# module_alu.net
KiCad netlist of a schematic drawn in EAGLE
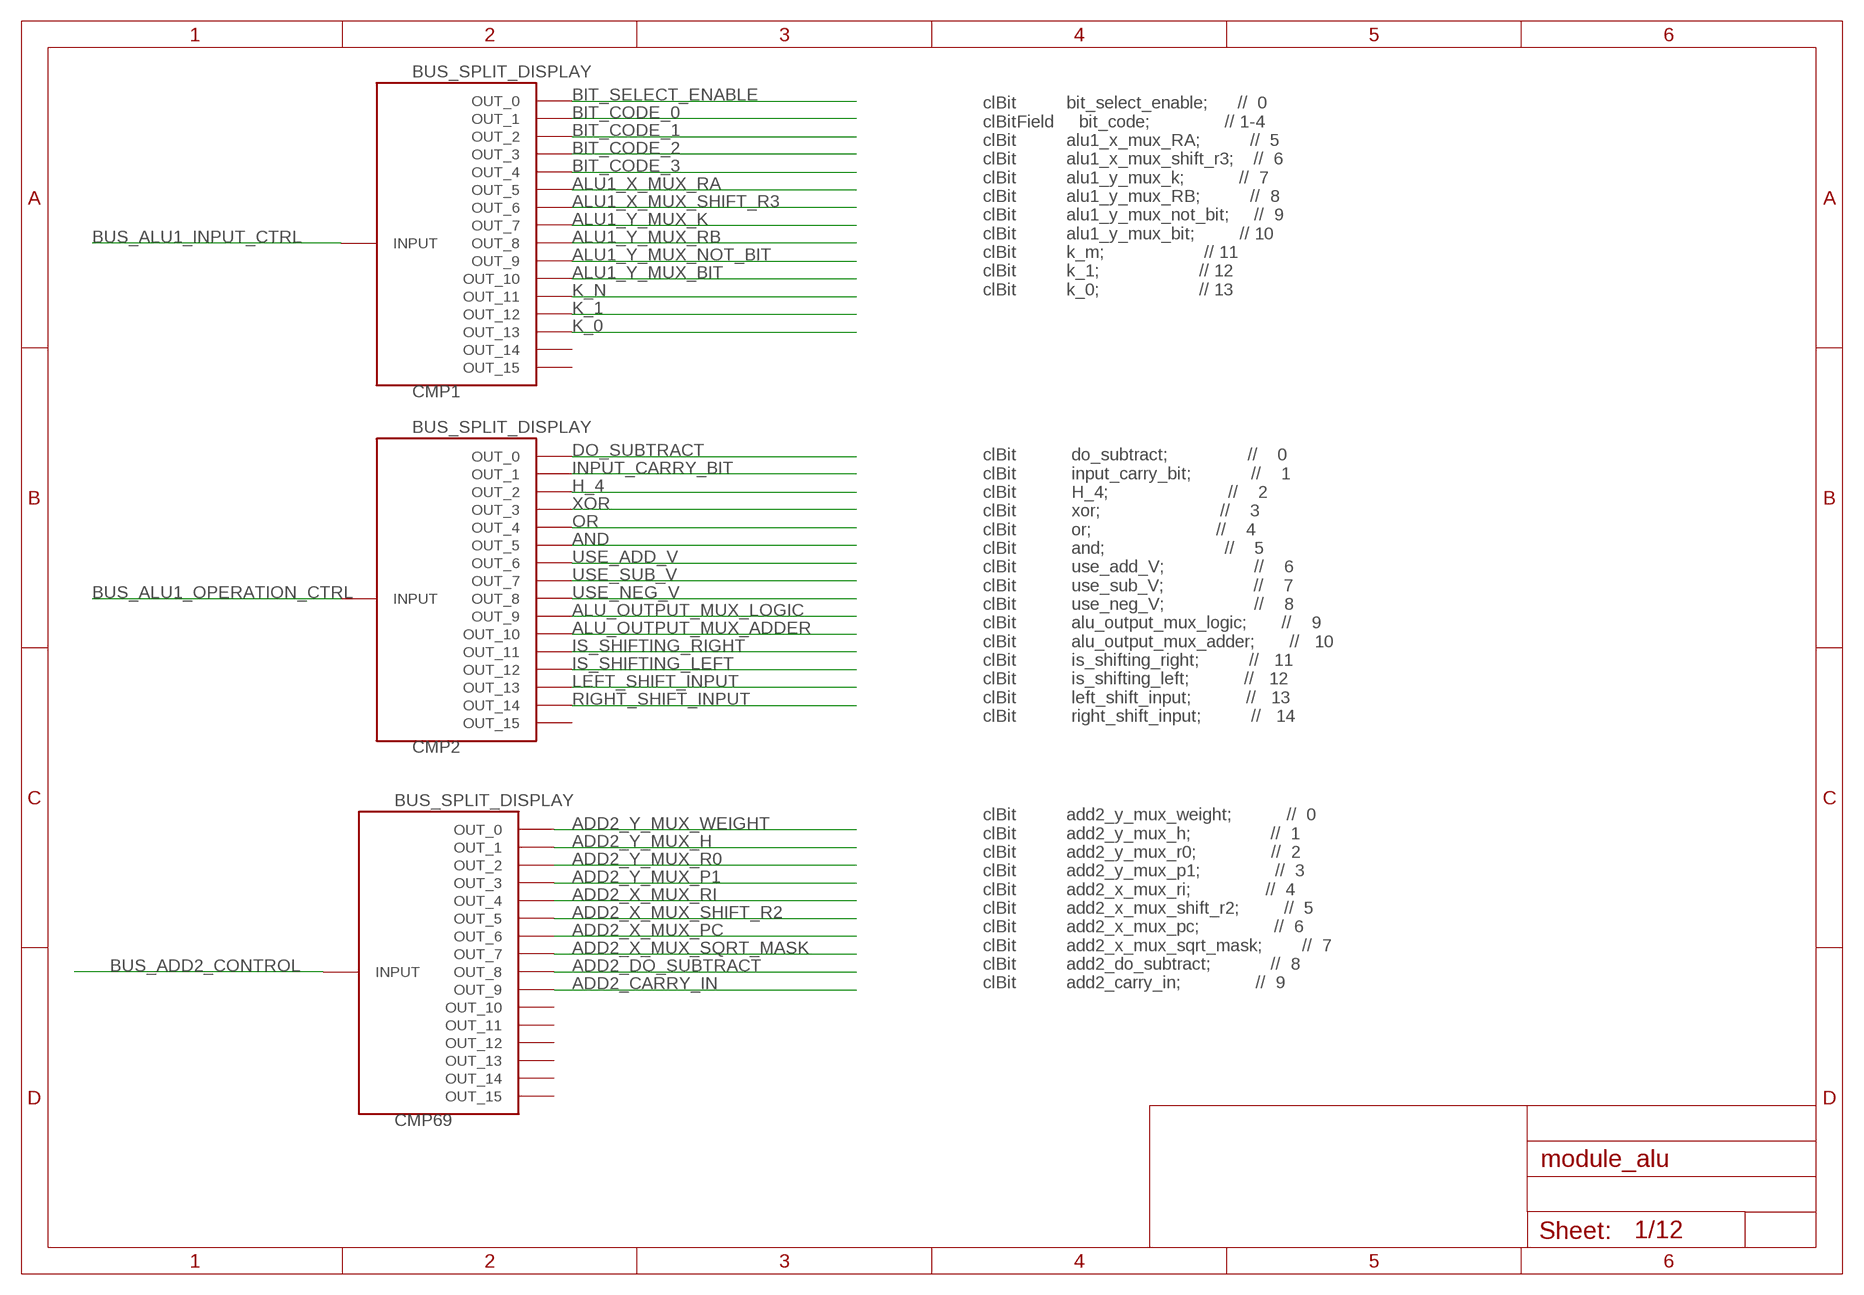
[diagram p0: schematic, sheet 1]
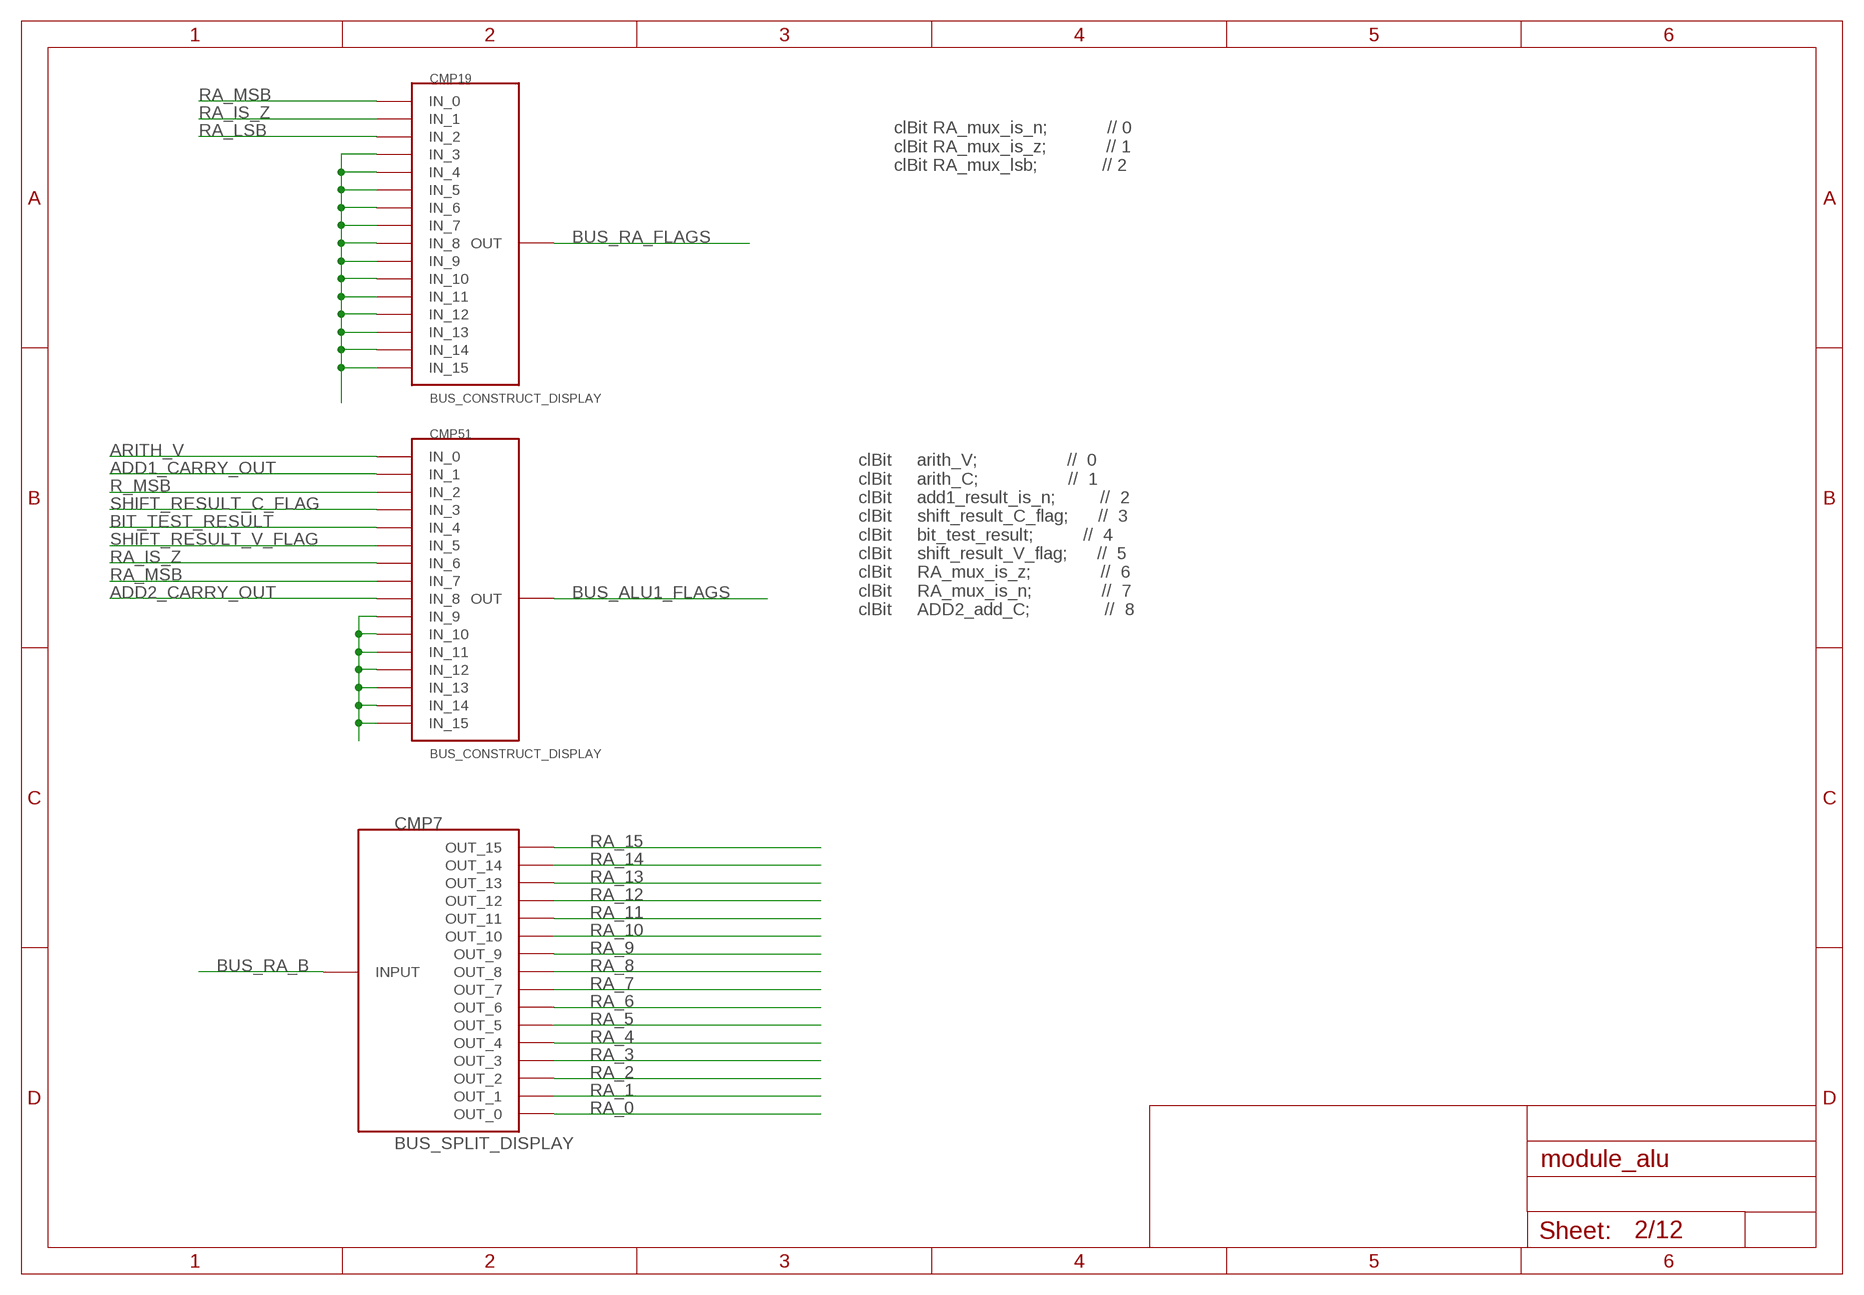
[diagram p1: schematic, sheet 2]
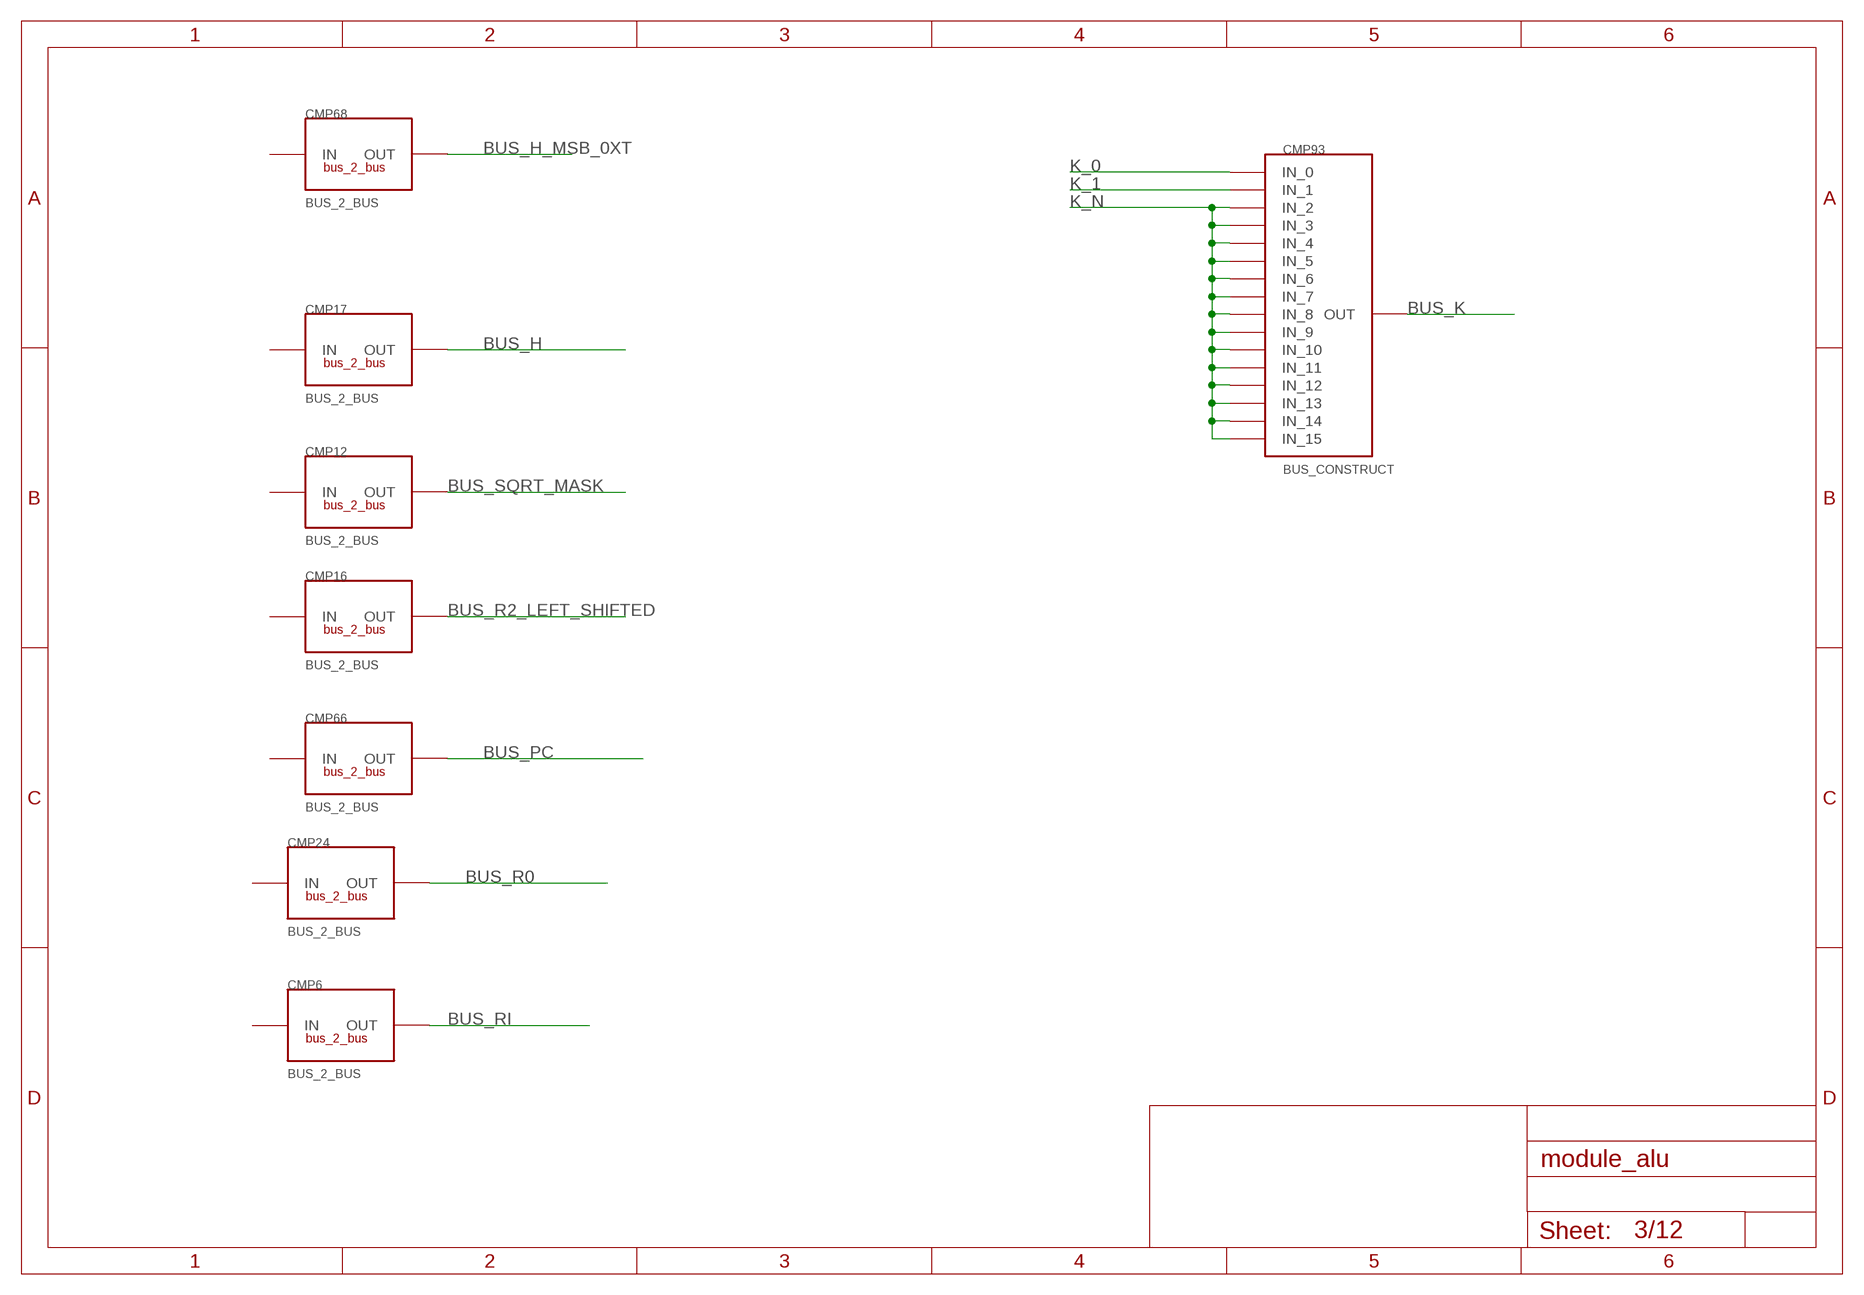
[diagram p2: schematic, sheet 3]
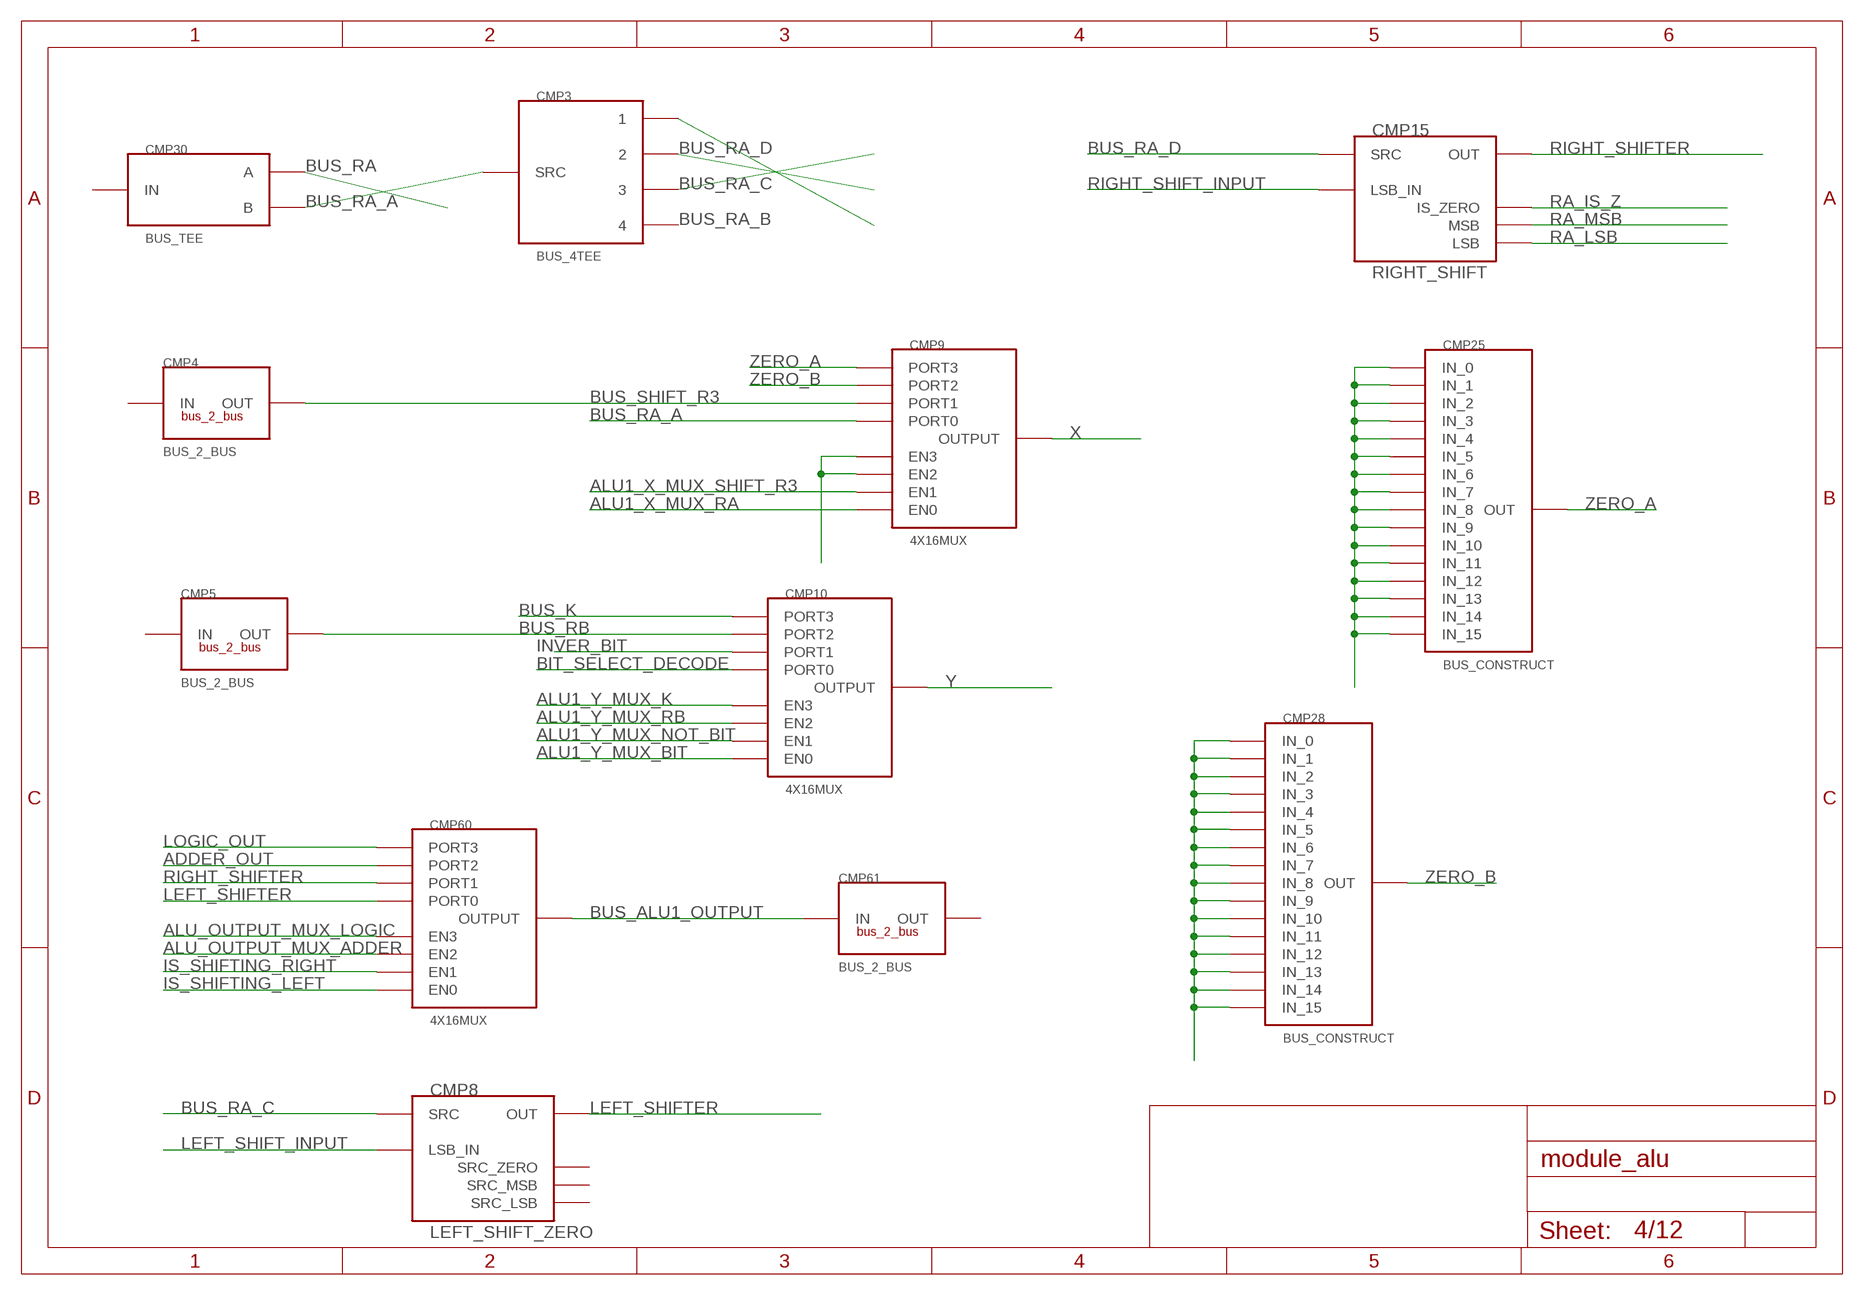
[diagram p3: schematic, sheet 4]
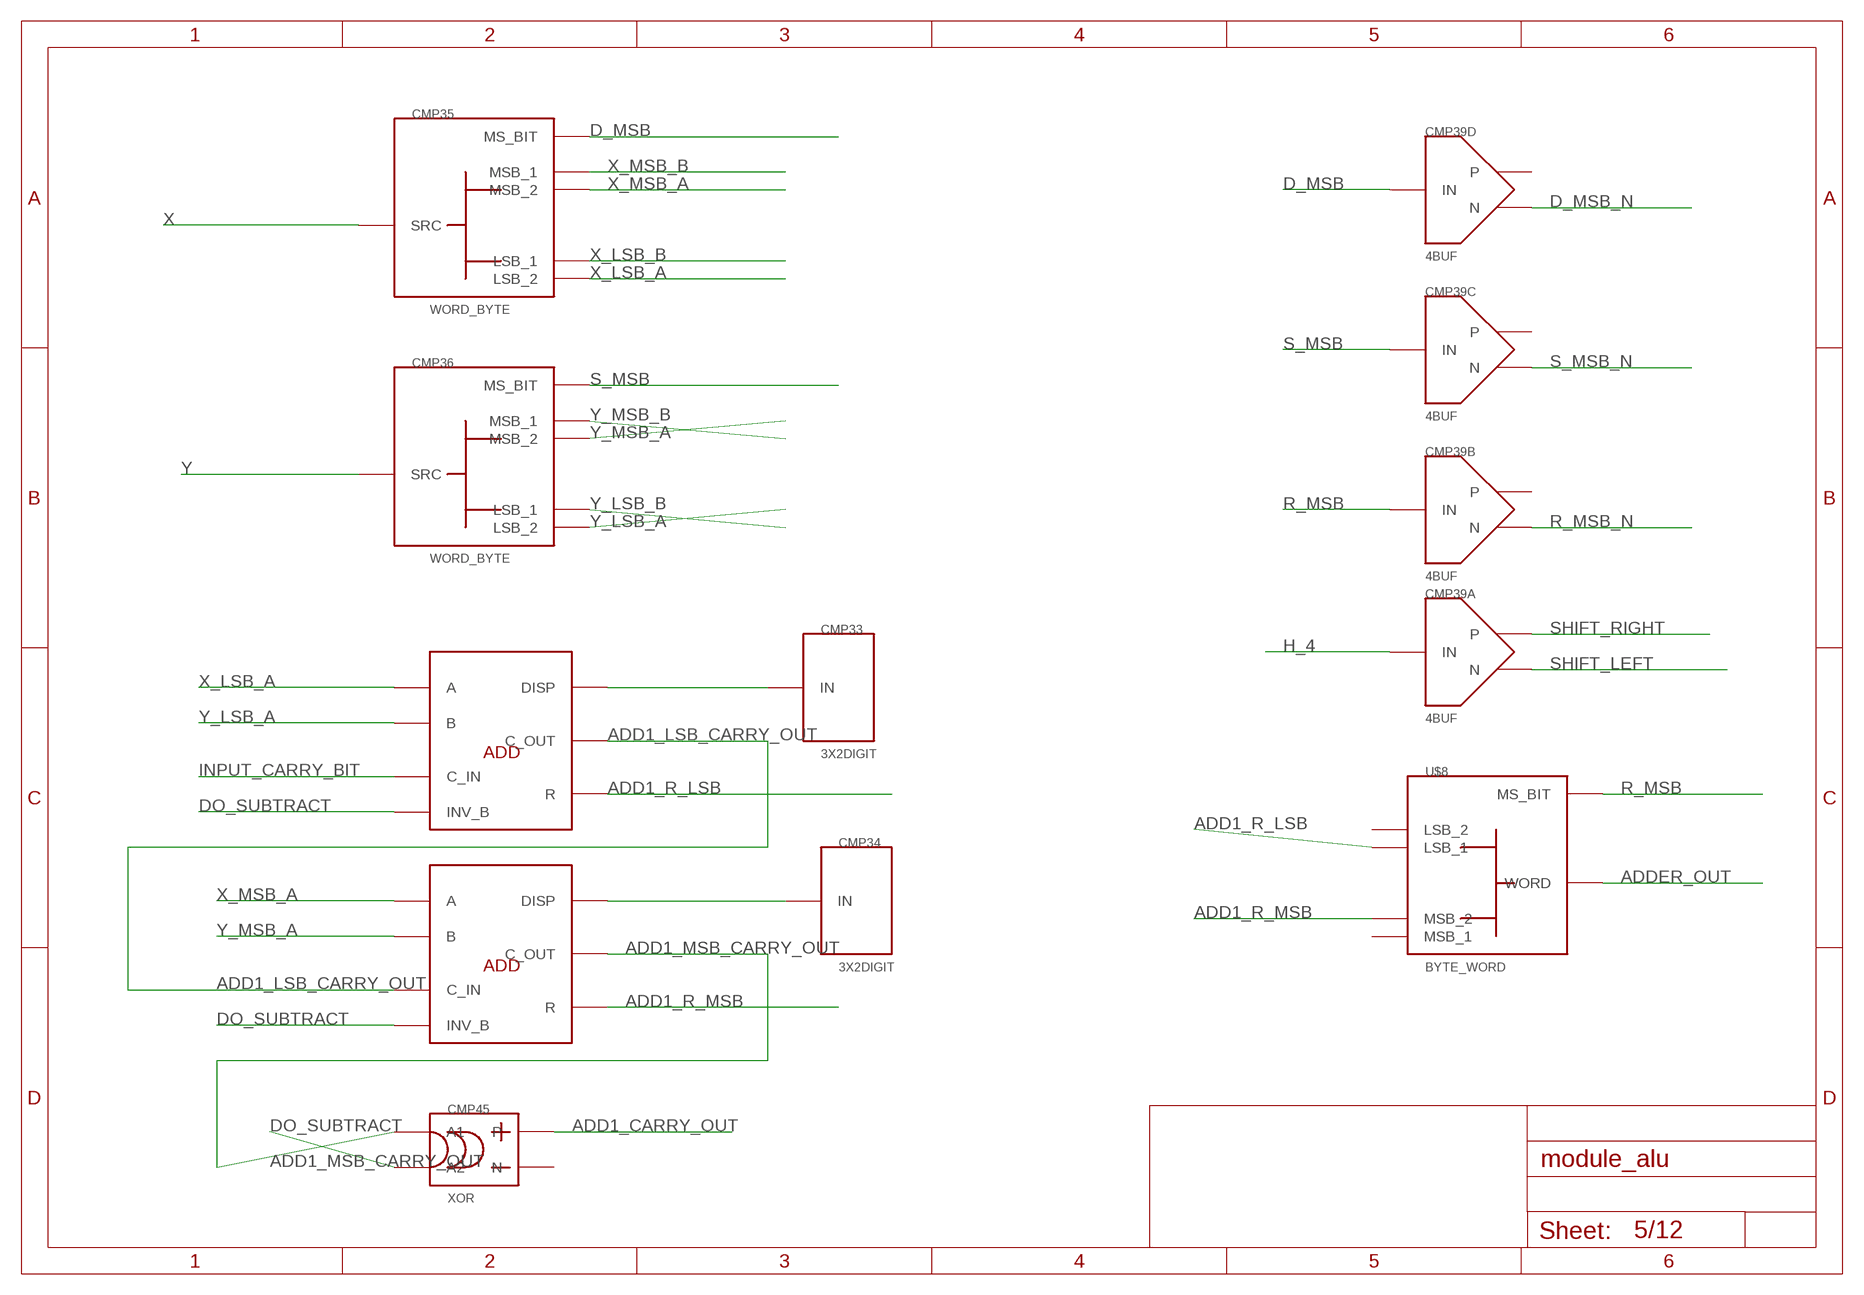
[diagram p4: schematic, sheet 5]
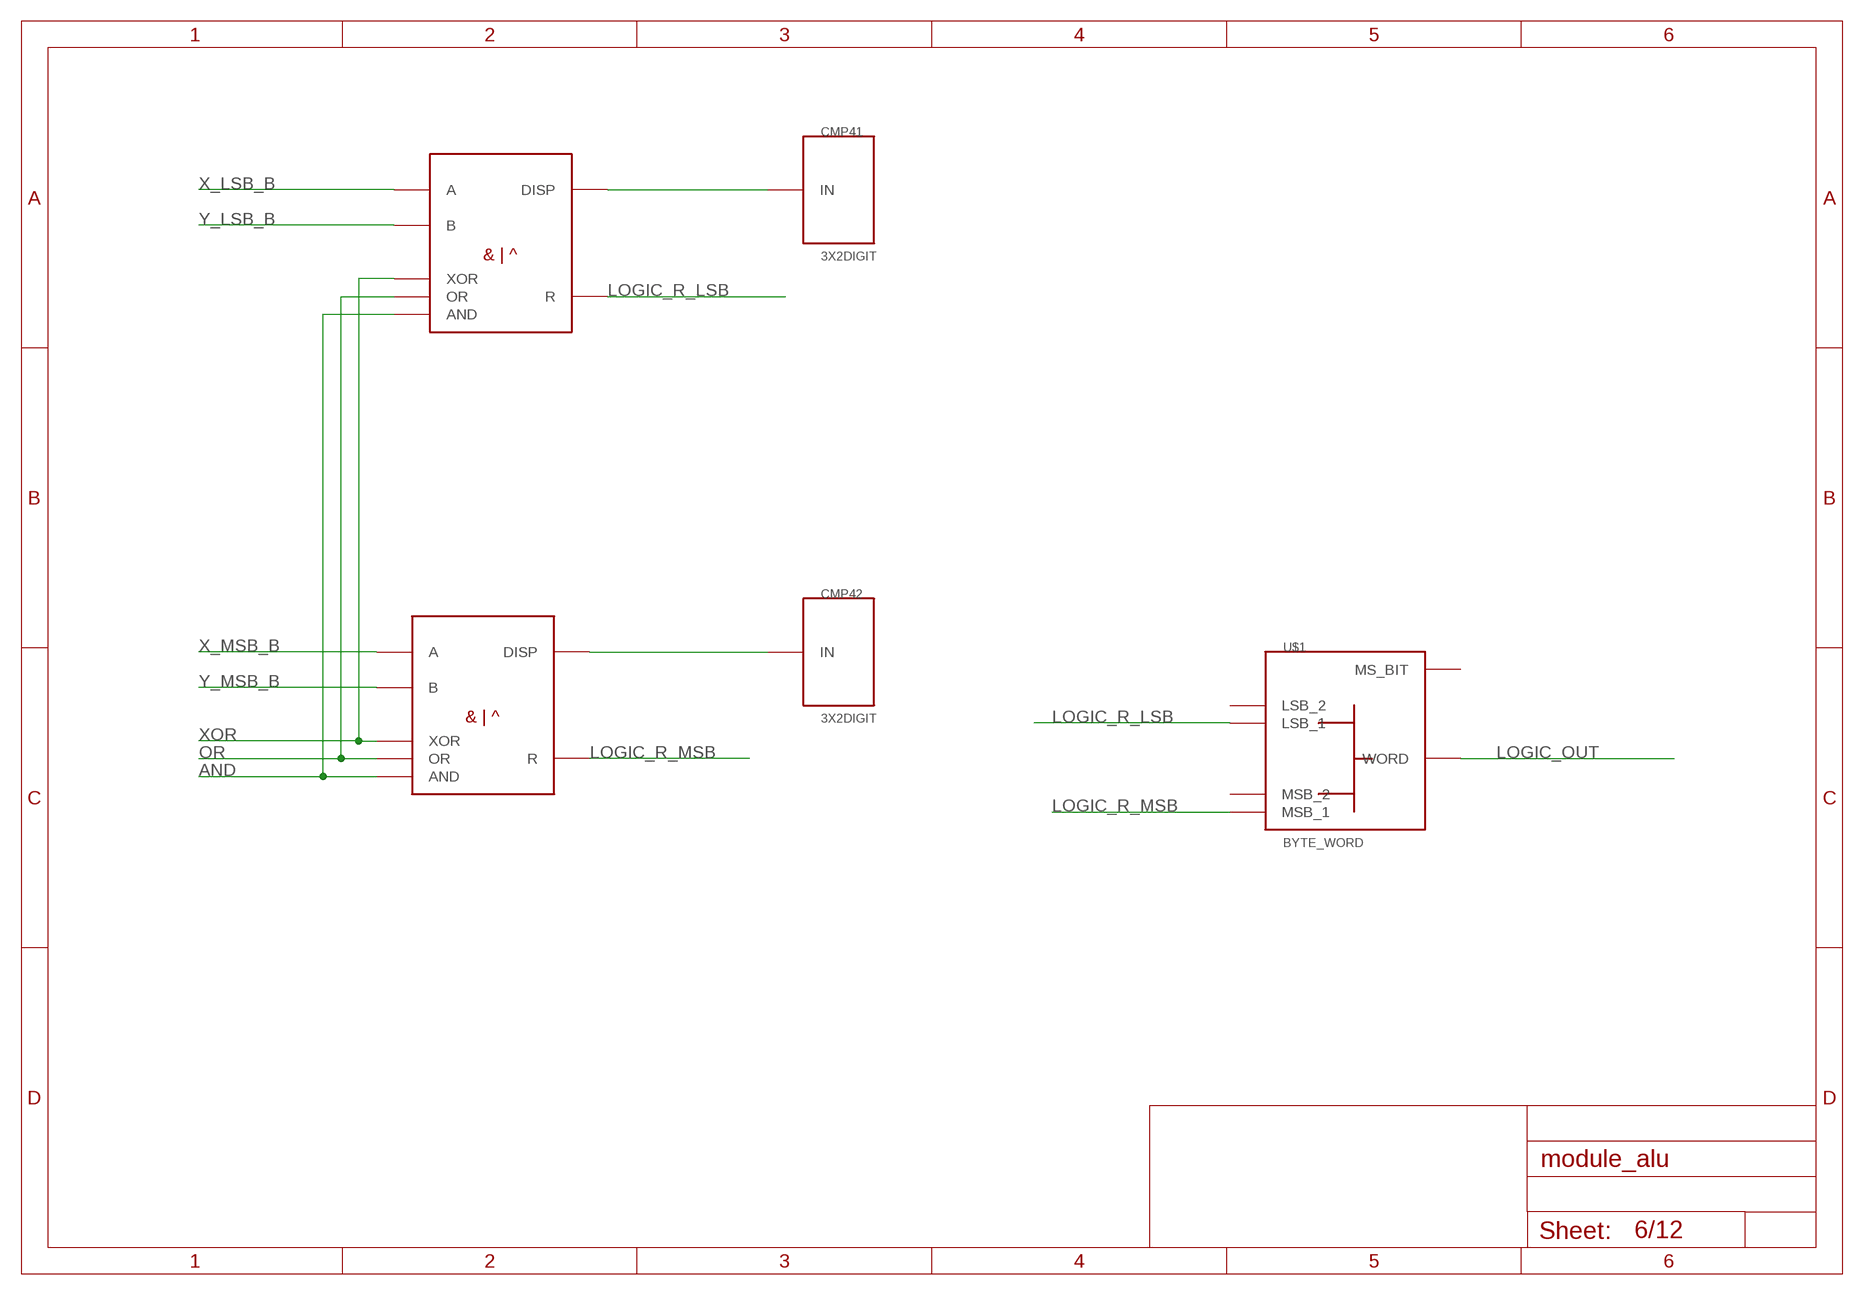
[diagram p5: schematic, sheet 6]
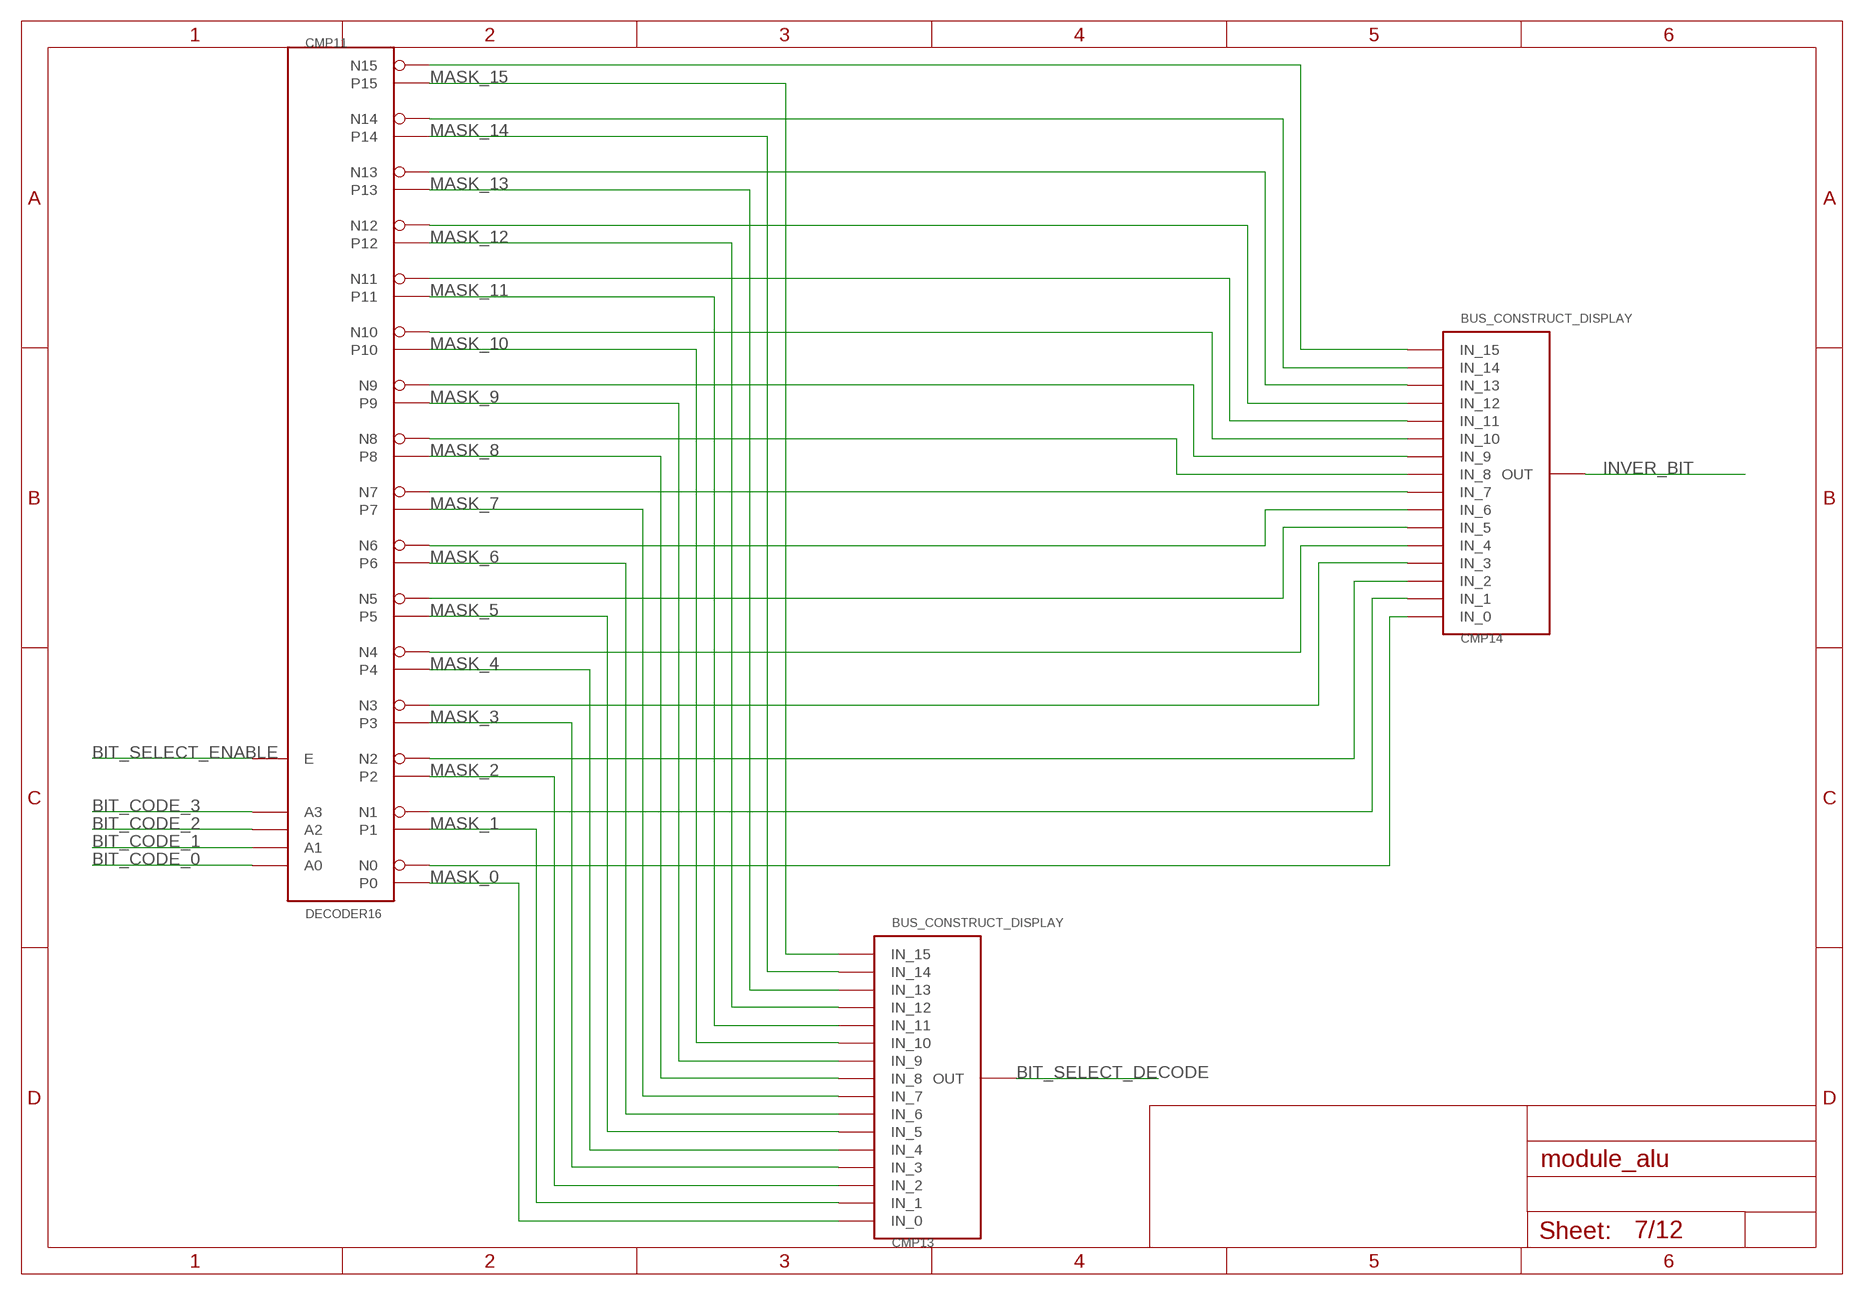
[diagram p6: schematic, sheet 7]
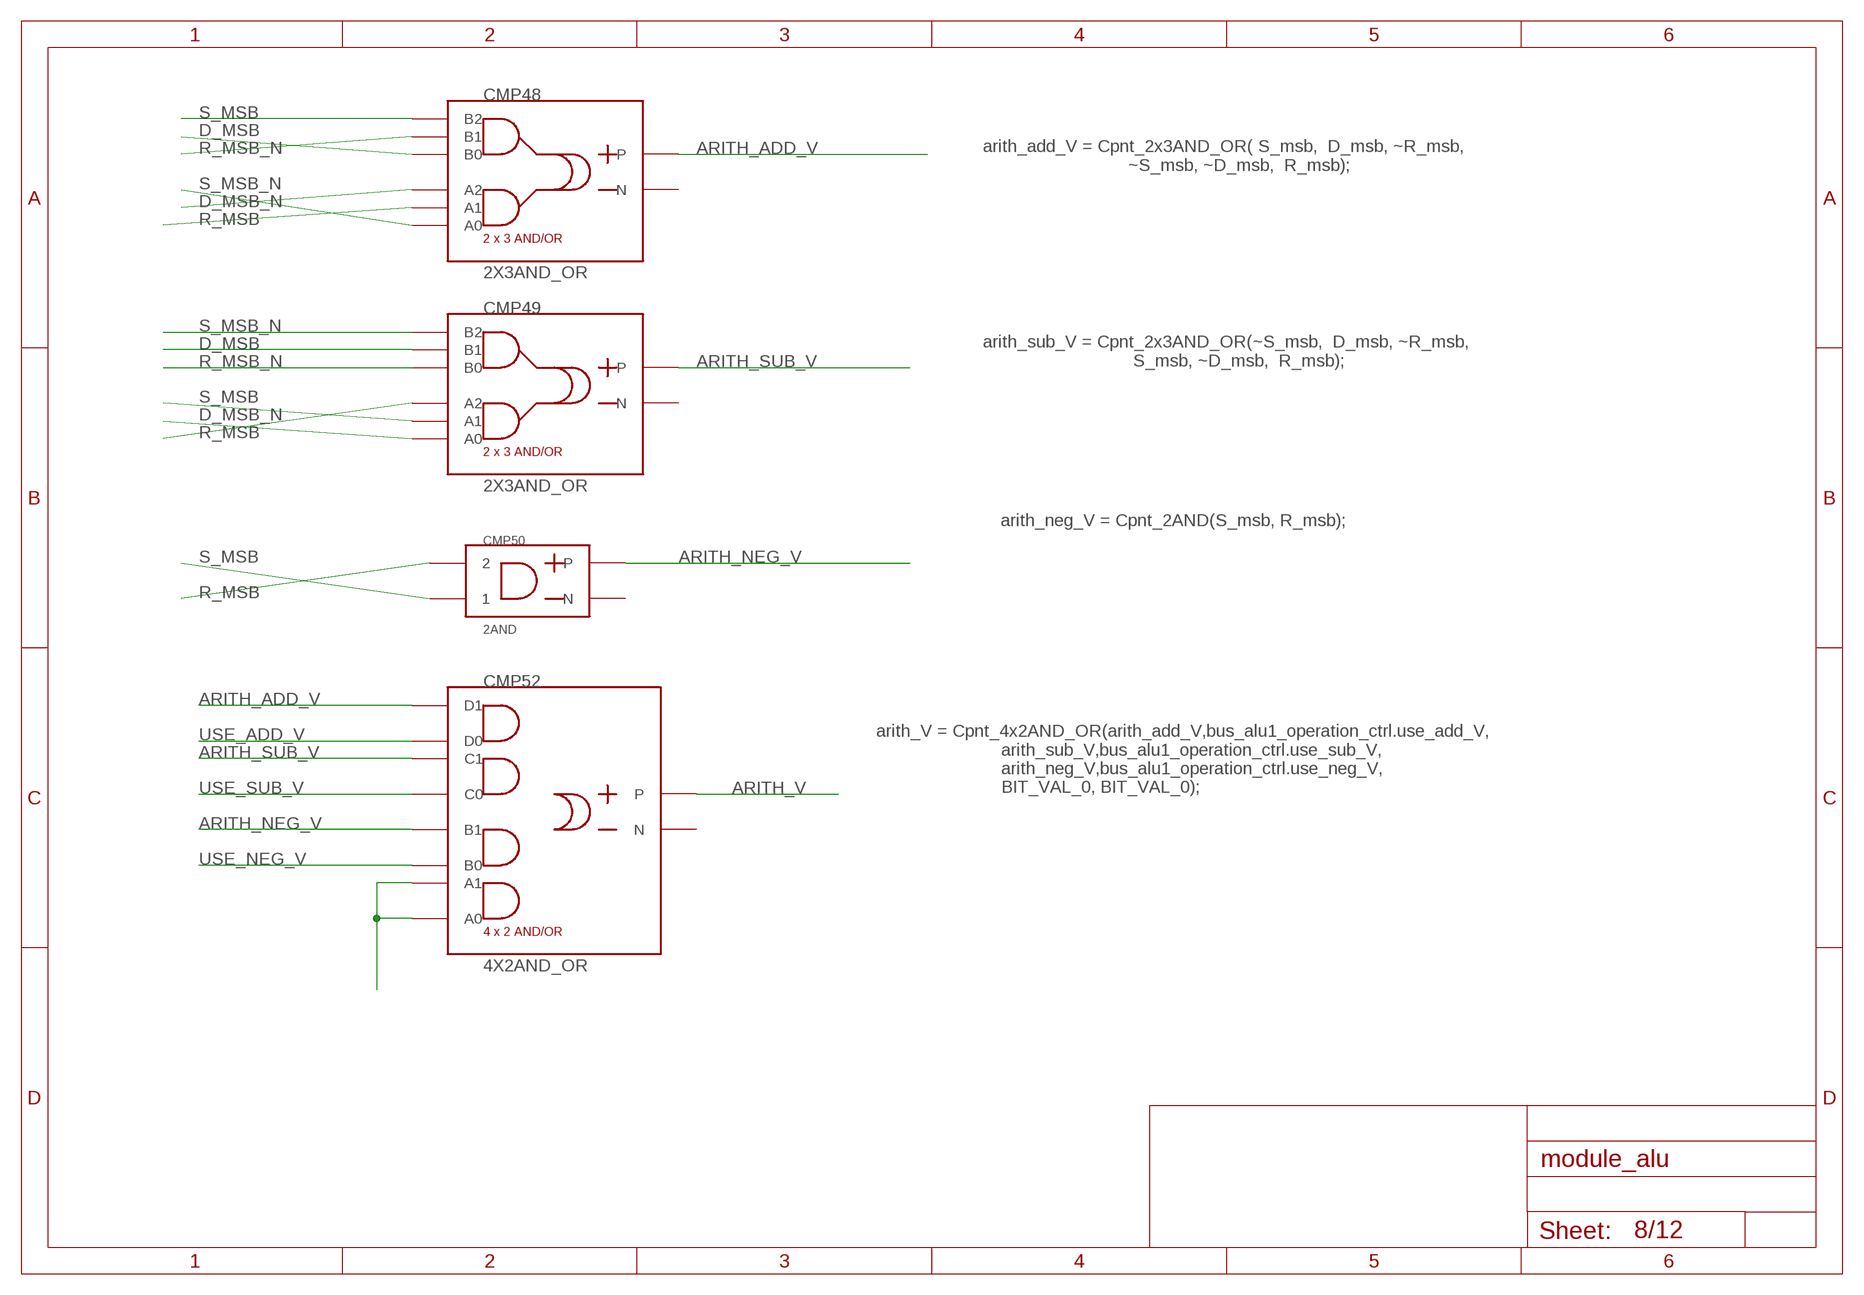
[diagram p7: schematic, sheet 8]
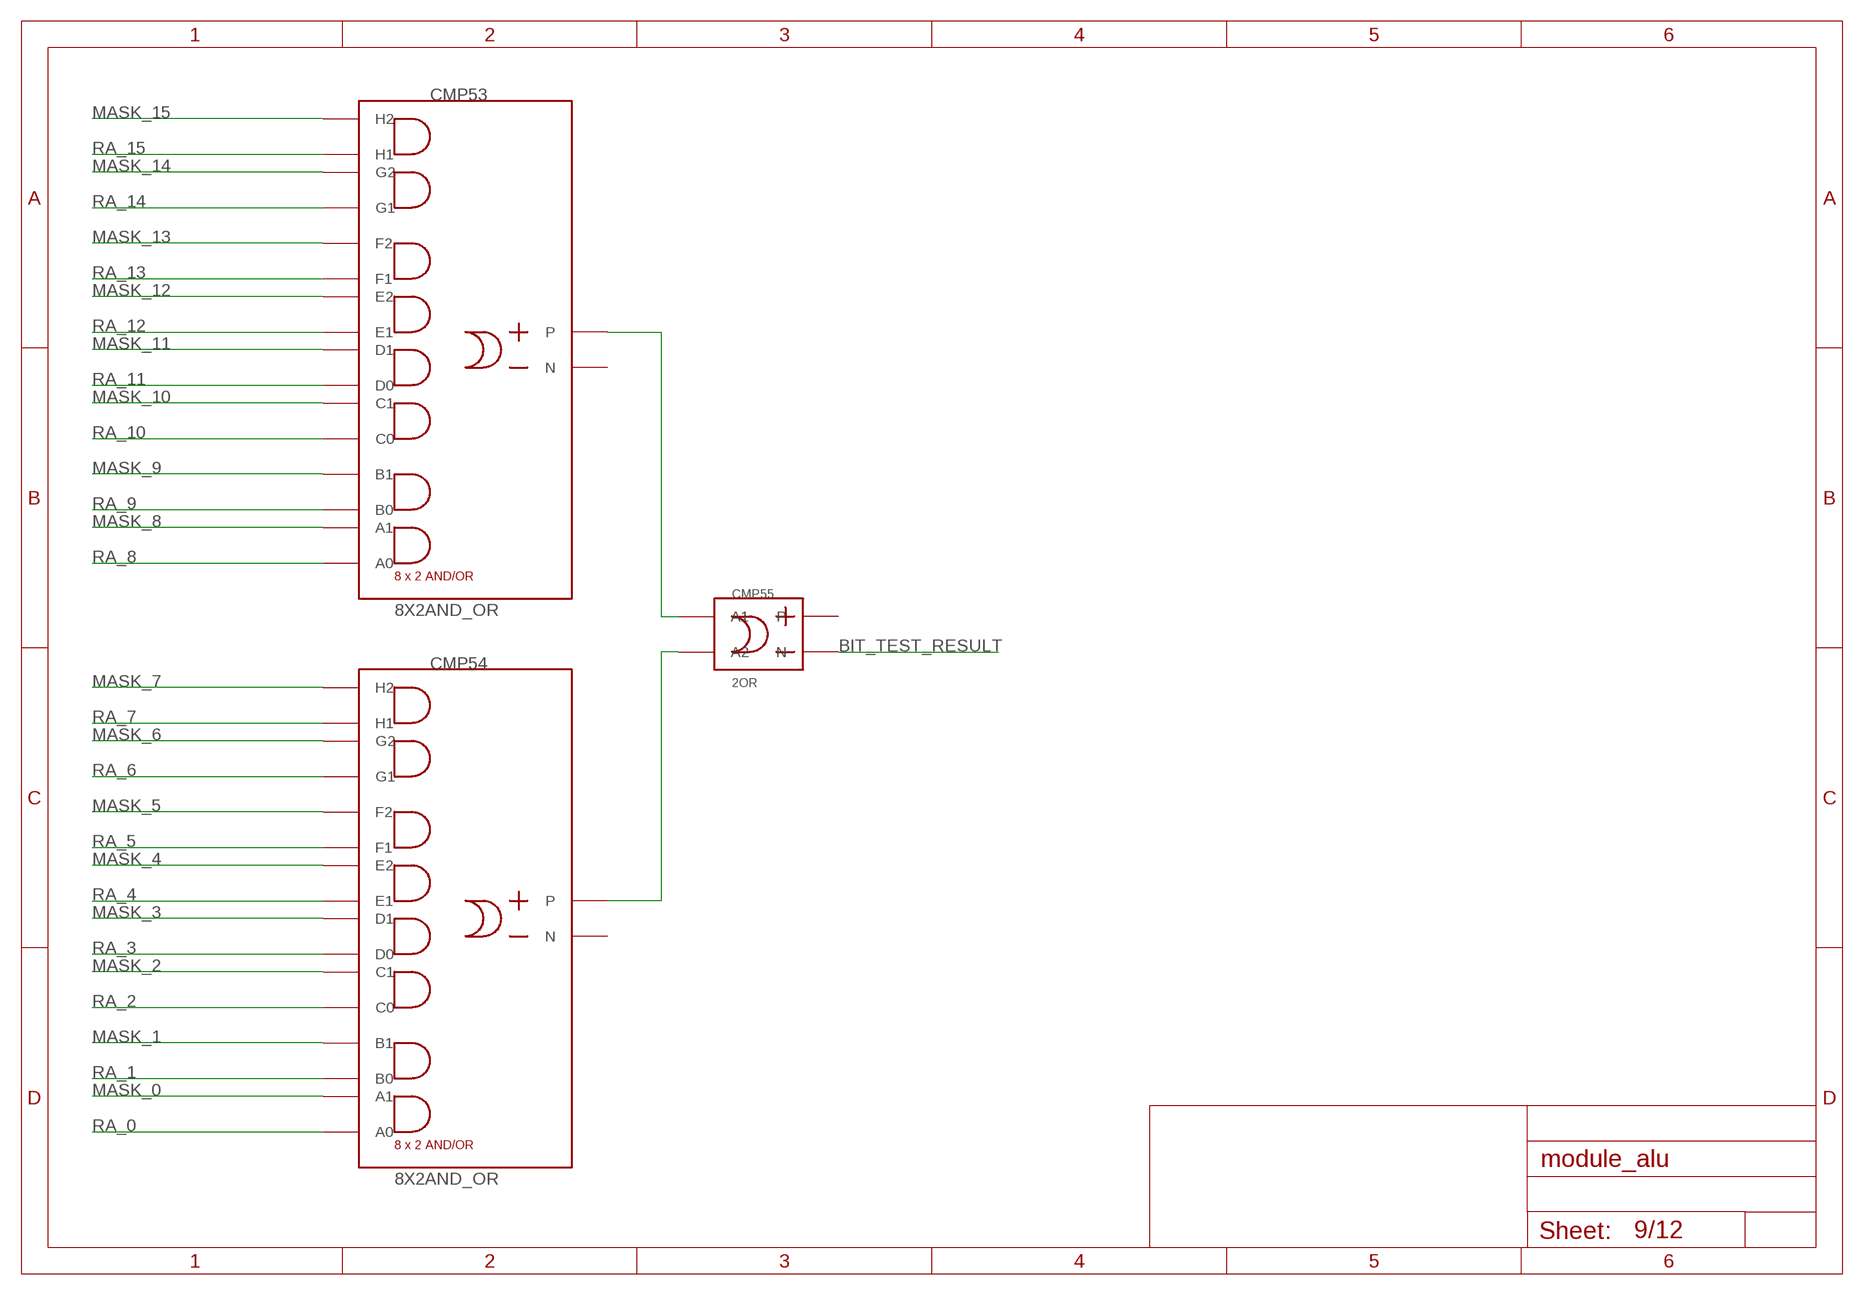
[diagram p8: schematic, sheet 9]
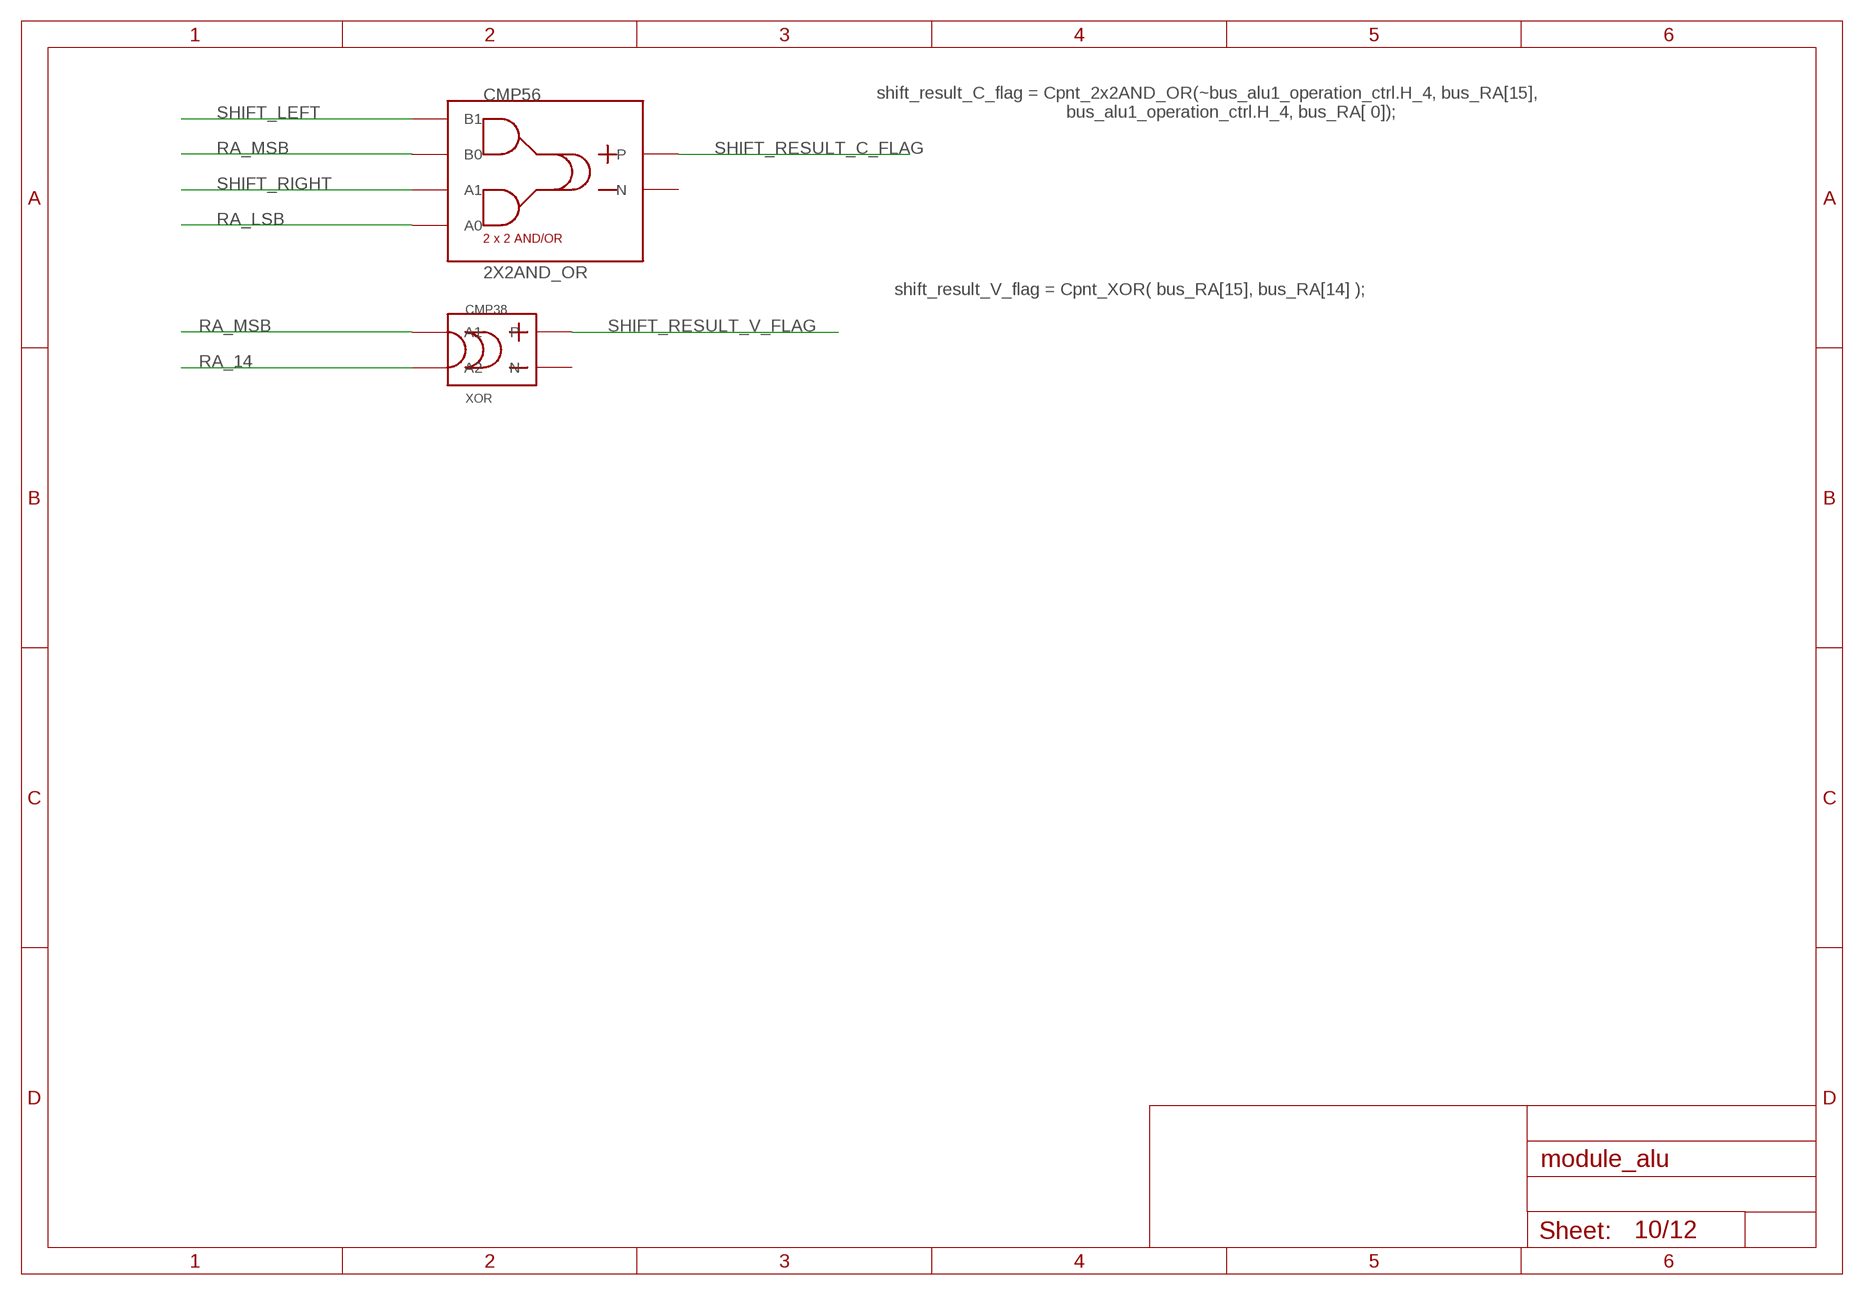
[diagram p9: schematic, sheet 10]
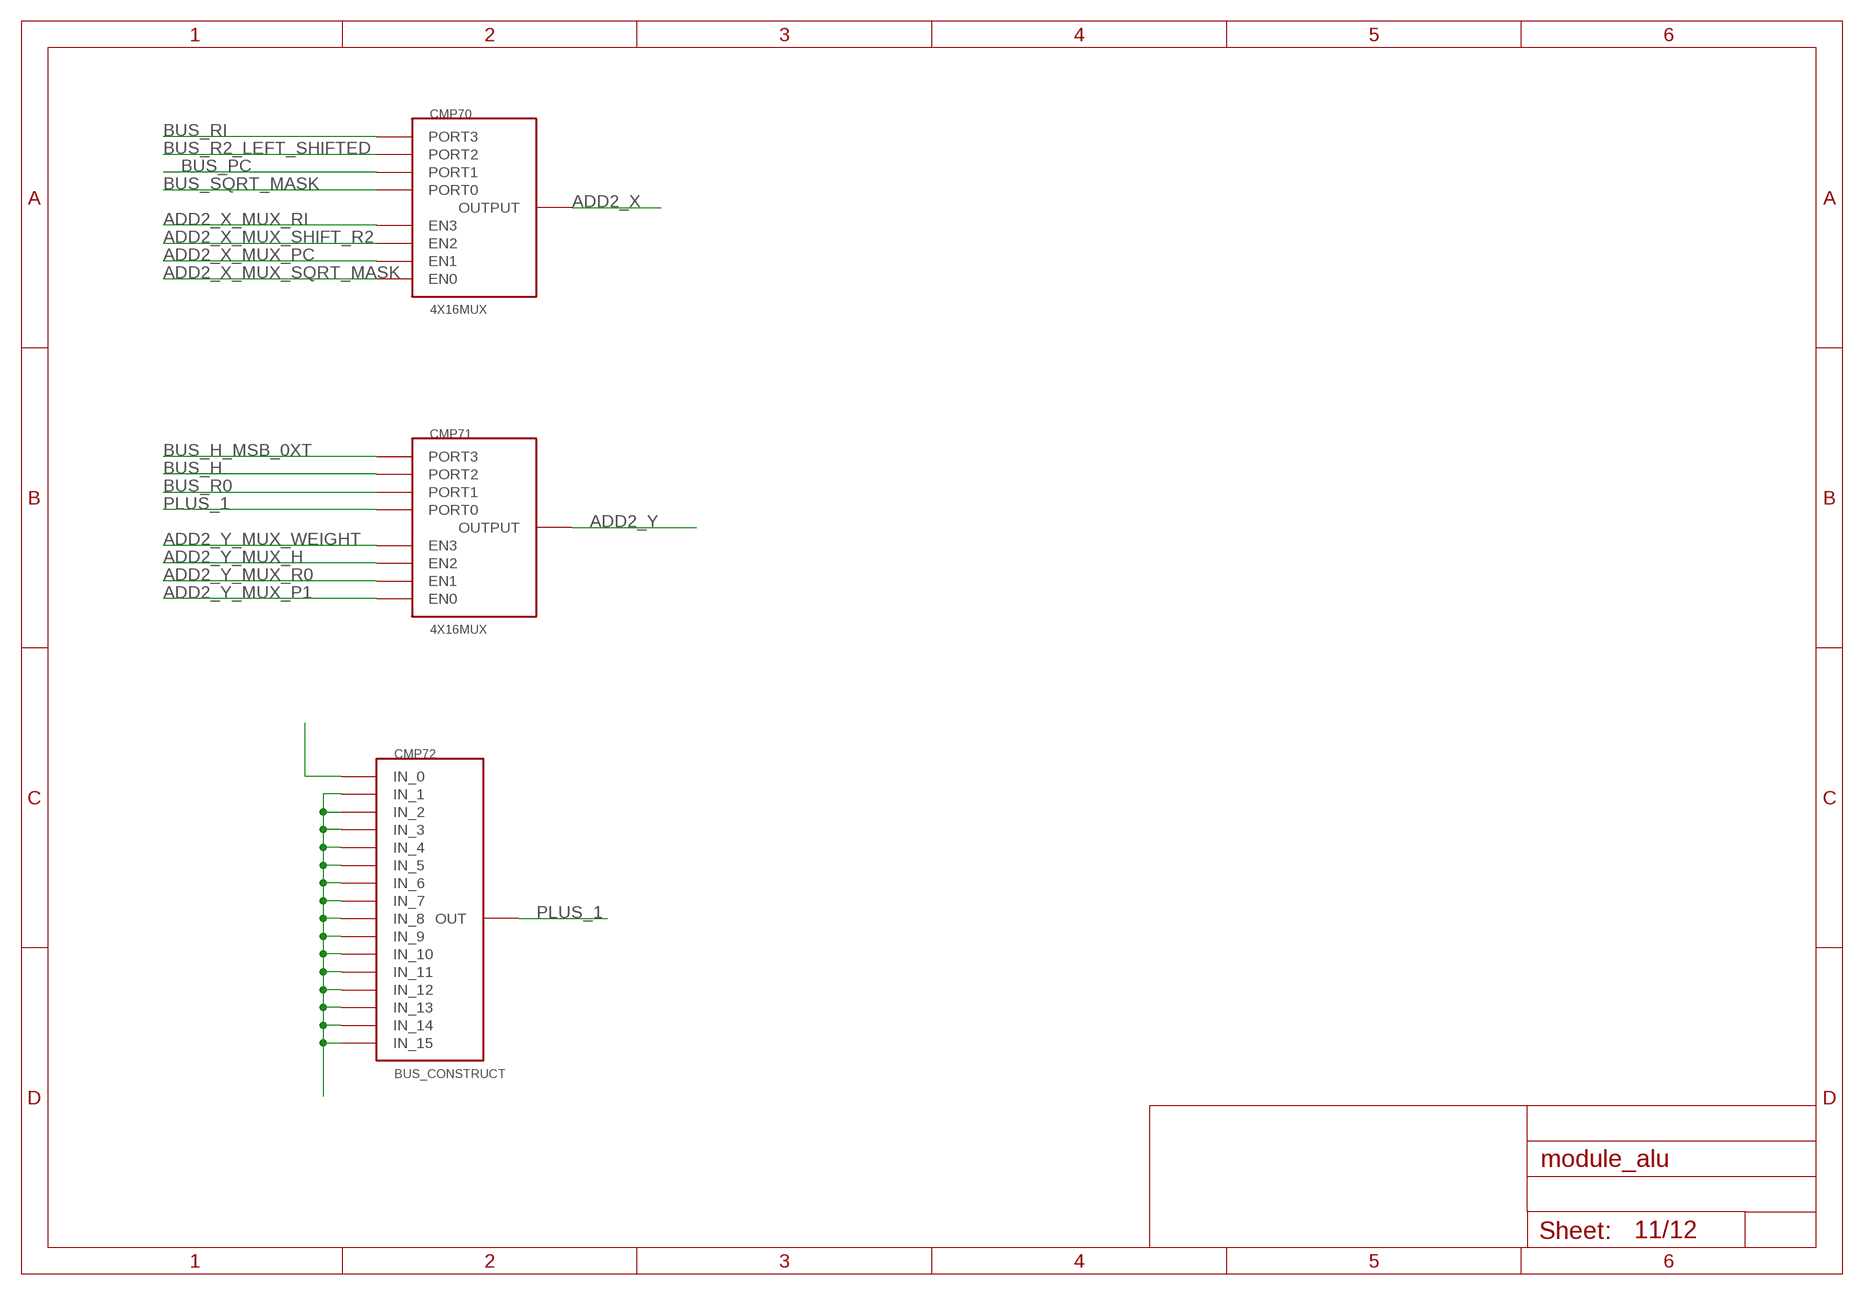
[diagram p10: schematic, sheet 11]
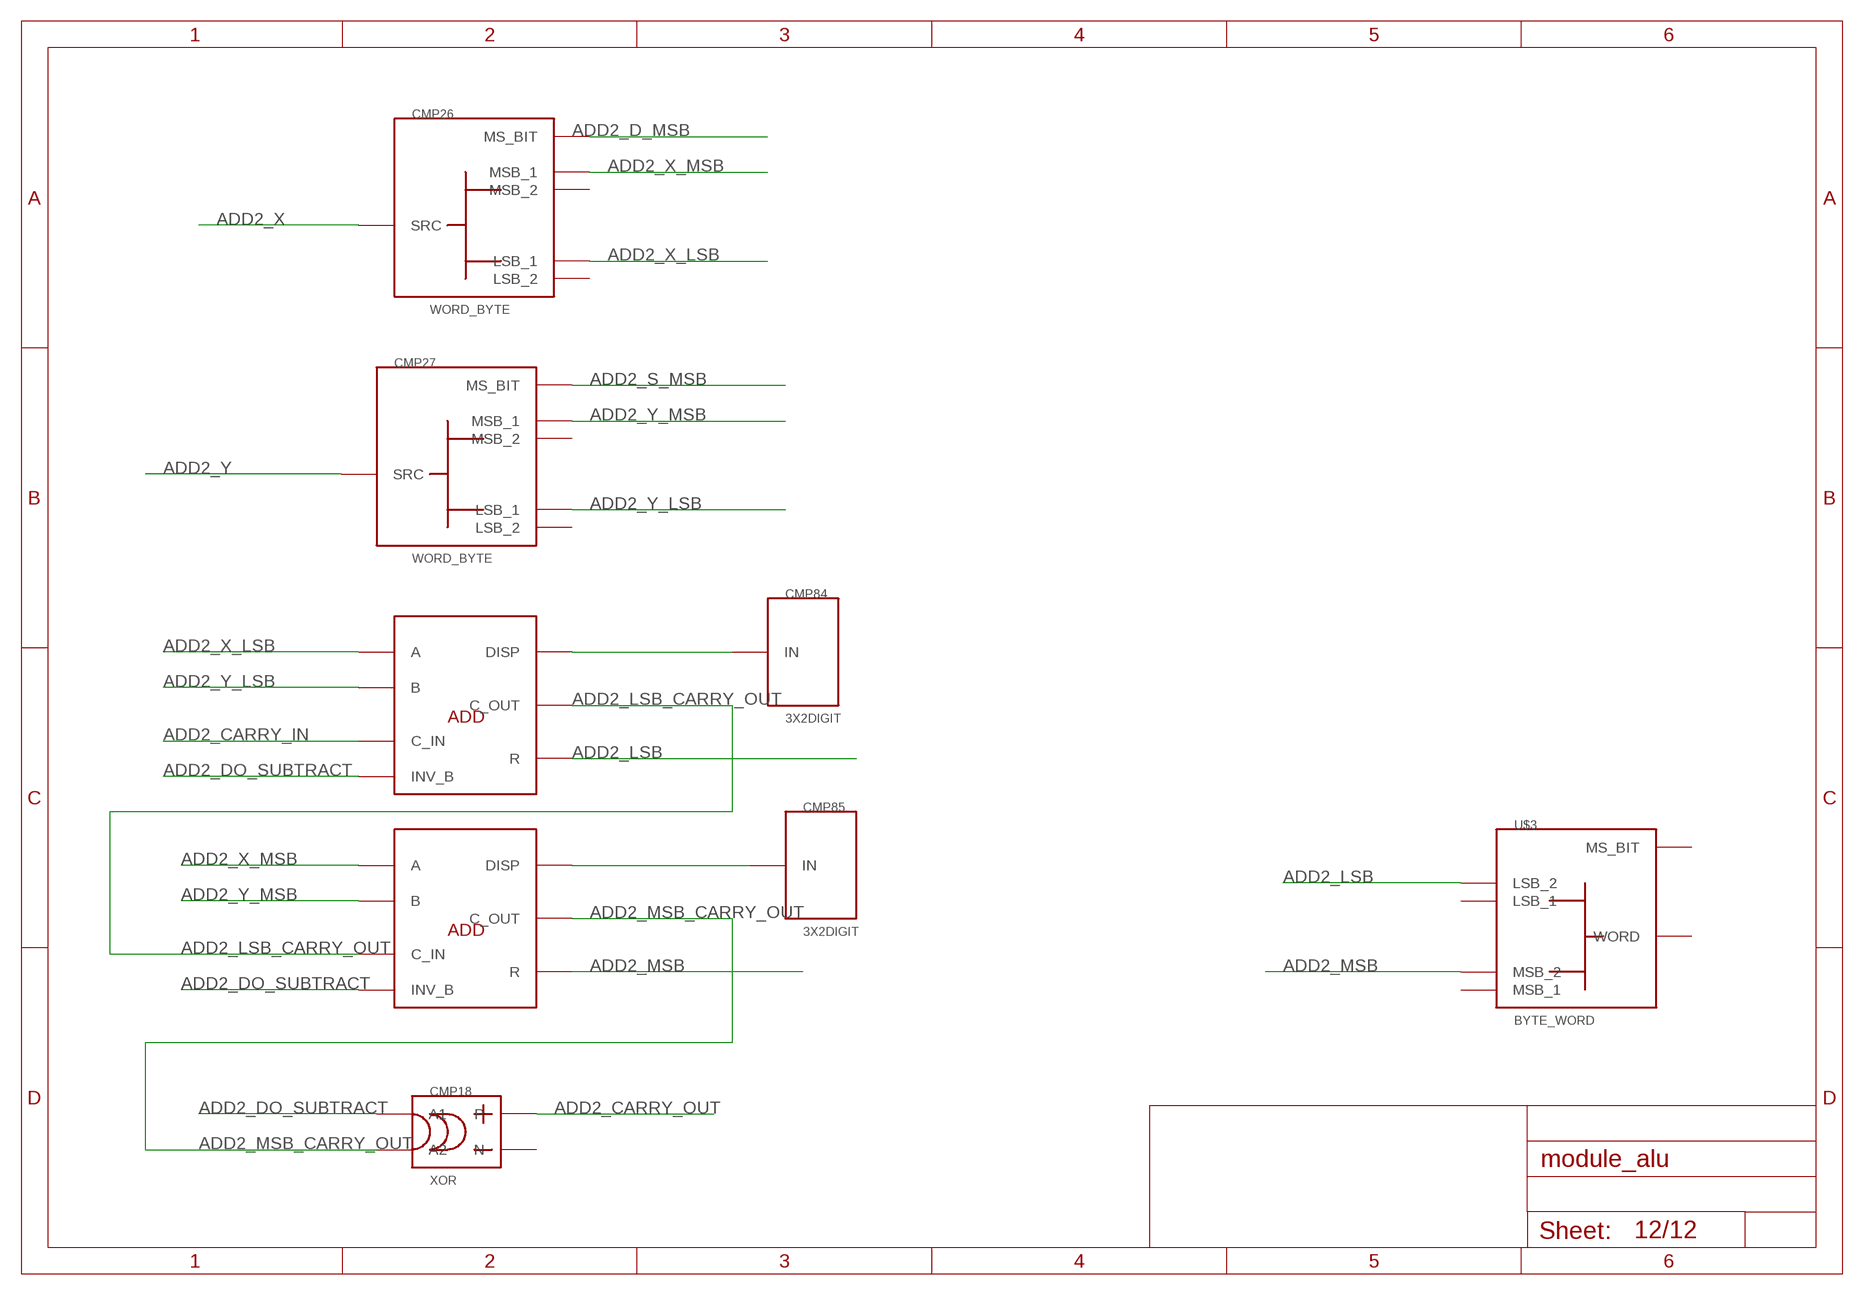
[diagram p11: schematic, sheet 12]

(export (version "E")
  (design (tool "Eeschema 10.0.6"))
  (components
    (comp (ref "CMP3")
      (value "BUS_4TEE")
      (footprint "eagle-import:BUS_4TEE")
      (libsource (lib "eagle-import") (part "BUS_4TEE"))
    )
    (comp (ref "CMP4")
      (value "BUS_2_BUS")
      (footprint "eagle-import:BUS2BUS")
      (libsource (lib "eagle-import") (part "BUS_2_BUS"))
    )
    (comp (ref "CMP5")
      (value "BUS_2_BUS")
      (footprint "eagle-import:BUS2BUS")
      (libsource (lib "eagle-import") (part "BUS_2_BUS"))
    )
    (comp (ref "CMP8")
      (value "LEFT_SHIFT_ZERO")
      (footprint "eagle-import:SHIFT_ZERO")
      (libsource (lib "eagle-import") (part "LEFT_SHIFT_ZERO"))
    )
    (comp (ref "CMP9")
      (value "4X16MUX")
      (footprint "eagle-import:4X16MUX")
      (libsource (lib "eagle-import") (part "4X16MUX"))
    )
    (comp (ref "CMP10")
      (value "4X16MUX")
      (footprint "eagle-import:4X16MUX")
      (libsource (lib "eagle-import") (part "4X16MUX"))
    )
    (comp (ref "CMP15")
      (value "RIGHT_SHIFT")
      (footprint "eagle-import:SHIFT_ZERO")
      (libsource (lib "eagle-import") (part "RIGHT_SHIFT"))
    )
    (comp (ref "CMP25")
      (value "BUS_CONSTRUCT")
      (footprint "eagle-import:BUS_SPLIT")
      (libsource (lib "eagle-import") (part "BUS_CONSTRUCT"))
    )
    (comp (ref "CMP28")
      (value "BUS_CONSTRUCT")
      (footprint "eagle-import:BUS_SPLIT")
      (libsource (lib "eagle-import") (part "BUS_CONSTRUCT"))
    )
    (comp (ref "CMP30")
      (value "BUS_TEE")
      (footprint "eagle-import:BUS_TEE")
      (libsource (lib "eagle-import") (part "BUS_TEE"))
    )
    (comp (ref "CMP60")
      (value "4X16MUX")
      (footprint "eagle-import:4X16MUX")
      (libsource (lib "eagle-import") (part "4X16MUX"))
    )
    (comp (ref "CMP61")
      (value "BUS_2_BUS")
      (footprint "eagle-import:BUS2BUS")
      (libsource (lib "eagle-import") (part "BUS_2_BUS"))
    )
    (comp (ref "CMP7")
      (value "BUS_SPLIT_DISPLAY")
      (footprint "eagle-import:BUS_SPLIT_DISPLAY")
      (libsource (lib "eagle-import") (part "BUS_SPLIT_DISPLAY"))
    )
    (comp (ref "CMP19")
      (value "BUS_CONSTRUCT_DISPLAY")
      (footprint "eagle-import:BUS_SPLIT_DISPLAY")
      (libsource (lib "eagle-import") (part "BUS_CONSTRUCT_DISPLAY"))
    )
    (comp (ref "CMP51")
      (value "BUS_CONSTRUCT_DISPLAY")
      (footprint "eagle-import:BUS_SPLIT_DISPLAY")
      (libsource (lib "eagle-import") (part "BUS_CONSTRUCT_DISPLAY"))
    )
    (comp (ref "CMP70")
      (value "4X16MUX")
      (footprint "eagle-import:4X16MUX")
      (libsource (lib "eagle-import") (part "4X16MUX"))
    )
    (comp (ref "CMP71")
      (value "4X16MUX")
      (footprint "eagle-import:4X16MUX")
      (libsource (lib "eagle-import") (part "4X16MUX"))
    )
    (comp (ref "CMP72")
      (value "BUS_CONSTRUCT")
      (footprint "eagle-import:BUS_SPLIT")
      (libsource (lib "eagle-import") (part "BUS_CONSTRUCT"))
    )
    (comp (ref "CMP38")
      (value "XOR")
      (footprint "eagle-import:XOR")
      (libsource (lib "eagle-import") (part "XOR"))
    )
    (comp (ref "CMP56")
      (value "2X2AND_OR")
      (footprint "eagle-import:2X2AND_OR")
      (libsource (lib "eagle-import") (part "2X2AND_OR"))
    )
    (comp (ref "CMP1")
      (value "BUS_SPLIT_DISPLAY")
      (footprint "eagle-import:BUS_SPLIT_DISPLAY")
      (libsource (lib "eagle-import") (part "BUS_SPLIT_DISPLAY"))
    )
    (comp (ref "CMP2")
      (value "BUS_SPLIT_DISPLAY")
      (footprint "eagle-import:BUS_SPLIT_DISPLAY")
      (libsource (lib "eagle-import") (part "BUS_SPLIT_DISPLAY"))
    )
    (comp (ref "CMP69")
      (value "BUS_SPLIT_DISPLAY")
      (footprint "eagle-import:BUS_SPLIT_DISPLAY")
      (libsource (lib "eagle-import") (part "BUS_SPLIT_DISPLAY"))
    )
    (comp (ref "CMP11")
      (value "DECODER16")
      (footprint "eagle-import:DECODER16")
      (libsource (lib "eagle-import") (part "DECODER16"))
    )
    (comp (ref "CMP13")
      (value "BUS_CONSTRUCT_DISPLAY")
      (footprint "eagle-import:BUS_SPLIT_DISPLAY")
      (libsource (lib "eagle-import") (part "BUS_CONSTRUCT_DISPLAY"))
    )
    (comp (ref "CMP14")
      (value "BUS_CONSTRUCT_DISPLAY")
      (footprint "eagle-import:BUS_SPLIT_DISPLAY")
      (libsource (lib "eagle-import") (part "BUS_CONSTRUCT_DISPLAY"))
    )
    (comp (ref "CMP31")
      (value "8BIT_ADD_SUB")
      (footprint "eagle-import:8BIT_ADD_SUB")
      (libsource (lib "eagle-import") (part "8BIT_ADD_SUB"))
    )
    (comp (ref "CMP32")
      (value "8BIT_ADD_SUB")
      (footprint "eagle-import:8BIT_ADD_SUB")
      (libsource (lib "eagle-import") (part "8BIT_ADD_SUB"))
    )
    (comp (ref "CMP33")
      (value "3X2DIGIT")
      (footprint "eagle-import:3X2DIGIT")
      (libsource (lib "eagle-import") (part "3X2DIGIT"))
    )
    (comp (ref "CMP34")
      (value "3X2DIGIT")
      (footprint "eagle-import:3X2DIGIT")
      (libsource (lib "eagle-import") (part "3X2DIGIT"))
    )
    (comp (ref "CMP35")
      (value "WORD_BYTE")
      (footprint "eagle-import:WORD_BYTE")
      (libsource (lib "eagle-import") (part "WORD_BYTE"))
    )
    (comp (ref "CMP36")
      (value "WORD_BYTE")
      (footprint "eagle-import:WORD_BYTE")
      (libsource (lib "eagle-import") (part "WORD_BYTE"))
    )
    (comp (ref "CMP39")
      (value "4BUF")
      (footprint "eagle-import:4BUF")
      (libsource (lib "eagle-import") (part "4BUF"))
    )
    (comp (ref "CMP45")
      (value "XOR")
      (footprint "eagle-import:XOR")
      (libsource (lib "eagle-import") (part "XOR"))
    )
    (comp (ref "U$8")
      (value "BYTE_WORD")
      (footprint "eagle-import:WORD_BYTE")
      (libsource (lib "eagle-import") (part "BYTE_WORD"))
    )
    (comp (ref "CMP48")
      (value "2X3AND_OR")
      (footprint "eagle-import:2X3AND_OR")
      (libsource (lib "eagle-import") (part "2X3AND_OR"))
    )
    (comp (ref "CMP49")
      (value "2X3AND_OR")
      (footprint "eagle-import:2X3AND_OR")
      (libsource (lib "eagle-import") (part "2X3AND_OR"))
    )
    (comp (ref "CMP50")
      (value "2AND")
      (footprint "eagle-import:2AND")
      (libsource (lib "eagle-import") (part "2AND"))
    )
    (comp (ref "CMP52")
      (value "4X2AND_OR")
      (footprint "eagle-import:4X2AND_OR")
      (libsource (lib "eagle-import") (part "4X2AND_OR"))
    )
    (comp (ref "CMP53")
      (value "8X2AND_OR")
      (footprint "eagle-import:8X2AND_OR")
      (libsource (lib "eagle-import") (part "8X2AND_OR"))
    )
    (comp (ref "CMP54")
      (value "8X2AND_OR")
      (footprint "eagle-import:8X2AND_OR")
      (libsource (lib "eagle-import") (part "8X2AND_OR"))
    )
    (comp (ref "CMP55")
      (value "2OR")
      (footprint "eagle-import:2OR")
      (libsource (lib "eagle-import") (part "2OR"))
    )
    (comp (ref "CMP18")
      (value "XOR")
      (footprint "eagle-import:XOR")
      (libsource (lib "eagle-import") (part "XOR"))
    )
    (comp (ref "CMP26")
      (value "WORD_BYTE")
      (footprint "eagle-import:WORD_BYTE")
      (libsource (lib "eagle-import") (part "WORD_BYTE"))
    )
    (comp (ref "CMP27")
      (value "WORD_BYTE")
      (footprint "eagle-import:WORD_BYTE")
      (libsource (lib "eagle-import") (part "WORD_BYTE"))
    )
    (comp (ref "CMP82")
      (value "8BIT_ADD_SUB")
      (footprint "eagle-import:8BIT_ADD_SUB")
      (libsource (lib "eagle-import") (part "8BIT_ADD_SUB"))
    )
    (comp (ref "CMP83")
      (value "8BIT_ADD_SUB")
      (footprint "eagle-import:8BIT_ADD_SUB")
      (libsource (lib "eagle-import") (part "8BIT_ADD_SUB"))
    )
    (comp (ref "CMP84")
      (value "3X2DIGIT")
      (footprint "eagle-import:3X2DIGIT")
      (libsource (lib "eagle-import") (part "3X2DIGIT"))
    )
    (comp (ref "CMP85")
      (value "3X2DIGIT")
      (footprint "eagle-import:3X2DIGIT")
      (libsource (lib "eagle-import") (part "3X2DIGIT"))
    )
    (comp (ref "U$3")
      (value "BYTE_WORD")
      (footprint "eagle-import:WORD_BYTE")
      (libsource (lib "eagle-import") (part "BYTE_WORD"))
    )
    (comp (ref "CMP41")
      (value "3X2DIGIT")
      (footprint "eagle-import:3X2DIGIT")
      (libsource (lib "eagle-import") (part "3X2DIGIT"))
    )
    (comp (ref "CMP42")
      (value "3X2DIGIT")
      (footprint "eagle-import:3X2DIGIT")
      (libsource (lib "eagle-import") (part "3X2DIGIT"))
    )
    (comp (ref "CMP46")
      (value "8BIT_LOGIC")
      (footprint "eagle-import:8BIT_LOGIC")
      (libsource (lib "eagle-import") (part "8BIT_LOGIC"))
    )
    (comp (ref "CMP47")
      (value "8BIT_LOGIC")
      (footprint "eagle-import:8BIT_LOGIC")
      (libsource (lib "eagle-import") (part "8BIT_LOGIC"))
    )
    (comp (ref "U$1")
      (value "BYTE_WORD")
      (footprint "eagle-import:WORD_BYTE")
      (libsource (lib "eagle-import") (part "BYTE_WORD"))
    )
    (comp (ref "CMP6")
      (value "BUS_2_BUS")
      (footprint "eagle-import:BUS2BUS")
      (libsource (lib "eagle-import") (part "BUS_2_BUS"))
    )
    (comp (ref "CMP12")
      (value "BUS_2_BUS")
      (footprint "eagle-import:BUS2BUS")
      (libsource (lib "eagle-import") (part "BUS_2_BUS"))
    )
    (comp (ref "CMP16")
      (value "BUS_2_BUS")
      (footprint "eagle-import:BUS2BUS")
      (libsource (lib "eagle-import") (part "BUS_2_BUS"))
    )
    (comp (ref "CMP17")
      (value "BUS_2_BUS")
      (footprint "eagle-import:BUS2BUS")
      (libsource (lib "eagle-import") (part "BUS_2_BUS"))
    )
    (comp (ref "CMP24")
      (value "BUS_2_BUS")
      (footprint "eagle-import:BUS2BUS")
      (libsource (lib "eagle-import") (part "BUS_2_BUS"))
    )
    (comp (ref "CMP66")
      (value "BUS_2_BUS")
      (footprint "eagle-import:BUS2BUS")
      (libsource (lib "eagle-import") (part "BUS_2_BUS"))
    )
    (comp (ref "CMP68")
      (value "BUS_2_BUS")
      (footprint "eagle-import:BUS2BUS")
      (libsource (lib "eagle-import") (part "BUS_2_BUS"))
    )
    (comp (ref "CMP93")
      (value "BUS_CONSTRUCT")
      (footprint "eagle-import:BUS_SPLIT")
      (libsource (lib "eagle-import") (part "BUS_CONSTRUCT"))
    )
  )
  (nets
    (net (code "1") (name "ADD1_CARRY_OUT") (class "Default")
      (node (ref "CMP45") (pin "OUT_P") (pinfunction "P_OUT_P") (pintype "output"))
      (node (ref "CMP51") (pin "P$2") (pinfunction "IN_1_P$2") (pintype "input"))
    )
    (net (code "2") (name "ADD1_LSB_CARRY_OUT") (class "Default")
      (node (ref "CMP31") (pin "C_OUT") (pinfunction "C_OUT_C_OUT") (pintype "output"))
      (node (ref "CMP32") (pin "C_IN") (pinfunction "C_IN_C_IN") (pintype "input"))
    )
    (net (code "3") (name "ADD1_MSB_CARRY_OUT") (class "Default")
      (node (ref "CMP32") (pin "C_OUT") (pinfunction "C_OUT_C_OUT") (pintype "output"))
      (node (ref "CMP45") (pin "P$1") (pinfunction "A1_P$1") (pintype "input"))
    )
    (net (code "4") (name "ADD1_R_LSB") (class "Default")
      (node (ref "CMP31") (pin "R") (pinfunction "R_R") (pintype "output"))
      (node (ref "U$8") (pin "LSB_1") (pinfunction "LSB_1_LSB_1") (pintype "input"))
    )
    (net (code "5") (name "ADD1_R_MSB") (class "Default")
      (node (ref "CMP32") (pin "R") (pinfunction "R_R") (pintype "output"))
      (node (ref "U$8") (pin "MSB_2") (pinfunction "MSB_2_MSB_2") (pintype "input"))
    )
    (net (code "6") (name "ADD2_CARRY_IN") (class "Default")
      (node (ref "CMP69") (pin "P$10") (pinfunction "OUT_9_P$10") (pintype "output"))
      (node (ref "CMP82") (pin "C_IN") (pinfunction "C_IN_C_IN") (pintype "input"))
    )
    (net (code "7") (name "ADD2_CARRY_OUT") (class "Default")
      (node (ref "CMP18") (pin "OUT_P") (pinfunction "P_OUT_P") (pintype "output"))
      (node (ref "CMP51") (pin "P$9") (pinfunction "IN_8_P$9") (pintype "input"))
    )
    (net (code "8") (name "ADD2_DO_SUBTRACT") (class "Default")
      (node (ref "CMP18") (pin "P$1") (pinfunction "A1_P$1") (pintype "input"))
      (node (ref "CMP69") (pin "P$9") (pinfunction "OUT_8_P$9") (pintype "output"))
      (node (ref "CMP82") (pin "INV_B") (pinfunction "INV_B_INV_B") (pintype "input"))
      (node (ref "CMP83") (pin "INV_B") (pinfunction "INV_B_INV_B") (pintype "input"))
    )
    (net (code "9") (name "ADD2_D_MSB") (class "Default")
      (node (ref "CMP26") (pin "MS_BIT") (pinfunction "MS_BIT_MS_BIT") (pintype "output"))
    )
    (net (code "10") (name "ADD2_LSB") (class "Default")
      (node (ref "CMP82") (pin "R") (pinfunction "R_R") (pintype "output"))
      (node (ref "U$3") (pin "LSB_2") (pinfunction "LSB_2_LSB_2") (pintype "input"))
    )
    (net (code "11") (name "ADD2_LSB_CARRY_OUT") (class "Default")
      (node (ref "CMP82") (pin "C_OUT") (pinfunction "C_OUT_C_OUT") (pintype "output"))
      (node (ref "CMP83") (pin "C_IN") (pinfunction "C_IN_C_IN") (pintype "input"))
    )
    (net (code "12") (name "ADD2_MSB") (class "Default")
      (node (ref "CMP83") (pin "R") (pinfunction "R_R") (pintype "output"))
      (node (ref "U$3") (pin "MSB_2") (pinfunction "MSB_2_MSB_2") (pintype "input"))
    )
    (net (code "13") (name "ADD2_MSB_CARRY_OUT") (class "Default")
      (node (ref "CMP18") (pin "P$2") (pinfunction "A2_P$2") (pintype "input"))
      (node (ref "CMP83") (pin "C_OUT") (pinfunction "C_OUT_C_OUT") (pintype "output"))
    )
    (net (code "14") (name "ADD2_S_MSB") (class "Default")
      (node (ref "CMP27") (pin "MS_BIT") (pinfunction "MS_BIT_MS_BIT") (pintype "output"))
    )
    (net (code "15") (name "ADD2_X") (class "Default")
      (node (ref "CMP26") (pin "SRC") (pinfunction "SRC_SRC") (pintype "input"))
      (node (ref "CMP70") (pin "PORTOUT") (pinfunction "OUTPUT_PORTOUT") (pintype "output"))
    )
    (net (code "16") (name "ADD2_X_LSB") (class "Default")
      (node (ref "CMP26") (pin "LSB_1") (pinfunction "LSB_1_LSB_1") (pintype "output"))
      (node (ref "CMP82") (pin "A") (pinfunction "A_A") (pintype "input"))
    )
    (net (code "17") (name "ADD2_X_MSB") (class "Default")
      (node (ref "CMP26") (pin "MSB_1") (pinfunction "MSB_1_MSB_1") (pintype "output"))
      (node (ref "CMP83") (pin "A") (pinfunction "A_A") (pintype "input"))
    )
    (net (code "18") (name "ADD2_X_MUX_PC") (class "Default")
      (node (ref "CMP69") (pin "P$7") (pinfunction "OUT_6_P$7") (pintype "output"))
      (node (ref "CMP70") (pin "EN1") (pinfunction "EN1_EN1") (pintype "input"))
    )
    (net (code "19") (name "ADD2_X_MUX_RI") (class "Default")
      (node (ref "CMP69") (pin "P$5") (pinfunction "OUT_4_P$5") (pintype "output"))
      (node (ref "CMP70") (pin "EN3") (pinfunction "EN3_EN3") (pintype "input"))
    )
    (net (code "20") (name "ADD2_X_MUX_SHIFT_R2") (class "Default")
      (node (ref "CMP69") (pin "P$6") (pinfunction "OUT_5_P$6") (pintype "output"))
      (node (ref "CMP70") (pin "EN2") (pinfunction "EN2_EN2") (pintype "input"))
    )
    (net (code "21") (name "ADD2_X_MUX_SQRT_MASK") (class "Default")
      (node (ref "CMP69") (pin "P$8") (pinfunction "OUT_7_P$8") (pintype "output"))
      (node (ref "CMP70") (pin "EN0") (pinfunction "EN0_EN0") (pintype "input"))
    )
    (net (code "22") (name "ADD2_Y") (class "Default")
      (node (ref "CMP27") (pin "SRC") (pinfunction "SRC_SRC") (pintype "input"))
      (node (ref "CMP71") (pin "PORTOUT") (pinfunction "OUTPUT_PORTOUT") (pintype "output"))
    )
    (net (code "23") (name "ADD2_Y_LSB") (class "Default")
      (node (ref "CMP27") (pin "LSB_1") (pinfunction "LSB_1_LSB_1") (pintype "output"))
      (node (ref "CMP82") (pin "B") (pinfunction "B_B") (pintype "input"))
    )
    (net (code "24") (name "ADD2_Y_MSB") (class "Default")
      (node (ref "CMP27") (pin "MSB_1") (pinfunction "MSB_1_MSB_1") (pintype "output"))
      (node (ref "CMP83") (pin "B") (pinfunction "B_B") (pintype "input"))
    )
    (net (code "25") (name "ADD2_Y_MUX_H") (class "Default")
      (node (ref "CMP69") (pin "P$2") (pinfunction "OUT_1_P$2") (pintype "output"))
      (node (ref "CMP71") (pin "EN2") (pinfunction "EN2_EN2") (pintype "input"))
    )
    (net (code "26") (name "ADD2_Y_MUX_P1") (class "Default")
      (node (ref "CMP69") (pin "P$4") (pinfunction "OUT_3_P$4") (pintype "output"))
      (node (ref "CMP71") (pin "EN0") (pinfunction "EN0_EN0") (pintype "input"))
    )
    (net (code "27") (name "ADD2_Y_MUX_R0") (class "Default")
      (node (ref "CMP69") (pin "P$3") (pinfunction "OUT_2_P$3") (pintype "output"))
      (node (ref "CMP71") (pin "EN1") (pinfunction "EN1_EN1") (pintype "input"))
    )
    (net (code "28") (name "ADD2_Y_MUX_WEIGHT") (class "Default")
      (node (ref "CMP69") (pin "P$1") (pinfunction "OUT_0_P$1") (pintype "output"))
      (node (ref "CMP71") (pin "EN3") (pinfunction "EN3_EN3") (pintype "input"))
    )
    (net (code "29") (name "ADDER_OUT") (class "Default")
      (node (ref "CMP60") (pin "PORT2") (pinfunction "PORT2_PORT2") (pintype "input"))
      (node (ref "U$8") (pin "SRC") (pinfunction "WORD_SRC") (pintype "output"))
    )
    (net (code "30") (name "ALU1_X_MUX_RA") (class "Default")
      (node (ref "CMP1") (pin "P$6") (pinfunction "OUT_5_P$6") (pintype "output"))
      (node (ref "CMP9") (pin "EN0") (pinfunction "EN0_EN0") (pintype "input"))
    )
    (net (code "31") (name "ALU1_X_MUX_SHIFT_R3") (class "Default")
      (node (ref "CMP1") (pin "P$7") (pinfunction "OUT_6_P$7") (pintype "output"))
      (node (ref "CMP9") (pin "EN1") (pinfunction "EN1_EN1") (pintype "input"))
    )
    (net (code "32") (name "ALU1_Y_MUX_BIT") (class "Default")
      (node (ref "CMP1") (pin "P$11") (pinfunction "OUT_10_P$11") (pintype "output"))
      (node (ref "CMP10") (pin "EN0") (pinfunction "EN0_EN0") (pintype "input"))
    )
    (net (code "33") (name "ALU1_Y_MUX_K") (class "Default")
      (node (ref "CMP1") (pin "P$8") (pinfunction "OUT_7_P$8") (pintype "output"))
      (node (ref "CMP10") (pin "EN3") (pinfunction "EN3_EN3") (pintype "input"))
    )
    (net (code "34") (name "ALU1_Y_MUX_NOT_BIT") (class "Default")
      (node (ref "CMP1") (pin "P$10") (pinfunction "OUT_9_P$10") (pintype "output"))
      (node (ref "CMP10") (pin "EN1") (pinfunction "EN1_EN1") (pintype "input"))
    )
    (net (code "35") (name "ALU1_Y_MUX_RB") (class "Default")
      (node (ref "CMP1") (pin "P$9") (pinfunction "OUT_8_P$9") (pintype "output"))
      (node (ref "CMP10") (pin "EN2") (pinfunction "EN2_EN2") (pintype "input"))
    )
    (net (code "36") (name "ALU_OUTPUT_MUX_ADDER") (class "Default")
      (node (ref "CMP2") (pin "P$11") (pinfunction "OUT_10_P$11") (pintype "output"))
      (node (ref "CMP60") (pin "EN2") (pinfunction "EN2_EN2") (pintype "input"))
    )
    (net (code "37") (name "ALU_OUTPUT_MUX_LOGIC") (class "Default")
      (node (ref "CMP2") (pin "P$10") (pinfunction "OUT_9_P$10") (pintype "output"))
      (node (ref "CMP60") (pin "EN3") (pinfunction "EN3_EN3") (pintype "input"))
    )
    (net (code "38") (name "AND") (class "Default")
      (node (ref "CMP2") (pin "P$6") (pinfunction "OUT_5_P$6") (pintype "output"))
      (node (ref "CMP46") (pin "AND") (pinfunction "AND_AND") (pintype "input"))
      (node (ref "CMP47") (pin "AND") (pinfunction "AND_AND") (pintype "input"))
    )
    (net (code "39") (name "ARITH_ADD_V") (class "Default")
      (node (ref "CMP48") (pin "OUT_P") (pinfunction "P_OUT_P") (pintype "output"))
      (node (ref "CMP52") (pin "P$8") (pinfunction "D1_P$8") (pintype "input"))
    )
    (net (code "40") (name "ARITH_NEG_V") (class "Default")
      (node (ref "CMP50") (pin "OUT_P") (pinfunction "P_OUT_P") (pintype "output"))
      (node (ref "CMP52") (pin "P$4") (pinfunction "B1_P$4") (pintype "input"))
    )
    (net (code "41") (name "ARITH_SUB_V") (class "Default")
      (node (ref "CMP49") (pin "OUT_P") (pinfunction "P_OUT_P") (pintype "output"))
      (node (ref "CMP52") (pin "P$6") (pinfunction "C1_P$6") (pintype "input"))
    )
    (net (code "42") (name "ARITH_V") (class "Default")
      (node (ref "CMP51") (pin "P$1") (pinfunction "IN_0_P$1") (pintype "input"))
      (node (ref "CMP52") (pin "OUT_P") (pinfunction "P_OUT_P") (pintype "output"))
    )
    (net (code "43") (name "BIT_CODE_0") (class "Default")
      (node (ref "CMP1") (pin "P$2") (pinfunction "OUT_1_P$2") (pintype "output"))
      (node (ref "CMP11") (pin "A0") (pinfunction "A0_A0") (pintype "input"))
    )
    (net (code "44") (name "BIT_CODE_1") (class "Default")
      (node (ref "CMP1") (pin "P$3") (pinfunction "OUT_2_P$3") (pintype "output"))
      (node (ref "CMP11") (pin "A1") (pinfunction "A1_A1") (pintype "input"))
    )
    (net (code "45") (name "BIT_CODE_2") (class "Default")
      (node (ref "CMP1") (pin "P$4") (pinfunction "OUT_3_P$4") (pintype "output"))
      (node (ref "CMP11") (pin "A2") (pinfunction "A2_A2") (pintype "input"))
    )
    (net (code "46") (name "BIT_CODE_3") (class "Default")
      (node (ref "CMP1") (pin "P$5") (pinfunction "OUT_4_P$5") (pintype "output"))
      (node (ref "CMP11") (pin "A3") (pinfunction "A3_A3") (pintype "input"))
    )
    (net (code "47") (name "BIT_SELECT_DECODE") (class "Default")
      (node (ref "CMP10") (pin "PORT0") (pinfunction "PORT0_PORT0") (pintype "input"))
      (node (ref "CMP13") (pin "INPUT") (pinfunction "OUT_INPUT") (pintype "output"))
    )
    (net (code "48") (name "BIT_SELECT_ENABLE") (class "Default")
      (node (ref "CMP1") (pin "P$1") (pinfunction "OUT_0_P$1") (pintype "output"))
      (node (ref "CMP11") (pin "E") (pinfunction "E_E") (pintype "input"))
    )
    (net (code "49") (name "BIT_TEST_RESULT") (class "Default")
      (node (ref "CMP51") (pin "P$5") (pinfunction "IN_4_P$5") (pintype "input"))
      (node (ref "CMP55") (pin "OUT_M") (pinfunction "N_OUT_M") (pintype "output"))
    )
    (net (code "50") (name "BUS_ADD2_CONTROL") (class "Default")
      (node (ref "CMP69") (pin "INPUT") (pinfunction "INPUT_INPUT") (pintype "input"))
    )
    (net (code "51") (name "BUS_ALU1_FLAGS") (class "Default")
      (node (ref "CMP51") (pin "INPUT") (pinfunction "OUT_INPUT") (pintype "output"))
    )
    (net (code "52") (name "BUS_ALU1_INPUT_CTRL") (class "Default")
      (node (ref "CMP1") (pin "INPUT") (pinfunction "INPUT_INPUT") (pintype "input"))
    )
    (net (code "53") (name "BUS_ALU1_OPERATION_CTRL") (class "Default")
      (node (ref "CMP2") (pin "INPUT") (pinfunction "INPUT_INPUT") (pintype "input"))
    )
    (net (code "54") (name "BUS_ALU1_OUTPUT") (class "Default")
      (node (ref "CMP60") (pin "PORTOUT") (pinfunction "OUTPUT_PORTOUT") (pintype "output"))
      (node (ref "CMP61") (pin "P$1") (pinfunction "IN_P$1") (pintype "input"))
    )
    (net (code "55") (name "BUS_H") (class "Default")
      (node (ref "CMP17") (pin "P$2") (pinfunction "OUT_P$2") (pintype "output"))
      (node (ref "CMP71") (pin "PORT2") (pinfunction "PORT2_PORT2") (pintype "input"))
    )
    (net (code "56") (name "BUS_H_MSB_0XT") (class "Default")
      (node (ref "CMP68") (pin "P$2") (pinfunction "OUT_P$2") (pintype "output"))
      (node (ref "CMP71") (pin "PORT3") (pinfunction "PORT3_PORT3") (pintype "input"))
    )
    (net (code "57") (name "BUS_K") (class "Default")
      (node (ref "CMP10") (pin "PORT3") (pinfunction "PORT3_PORT3") (pintype "input"))
      (node (ref "CMP93") (pin "INPUT") (pinfunction "OUT_INPUT") (pintype "output"))
    )
    (net (code "58") (name "BUS_PC") (class "Default")
      (node (ref "CMP66") (pin "P$2") (pinfunction "OUT_P$2") (pintype "output"))
      (node (ref "CMP70") (pin "PORT1") (pinfunction "PORT1_PORT1") (pintype "input"))
    )
    (net (code "59") (name "BUS_R0") (class "Default")
      (node (ref "CMP24") (pin "P$2") (pinfunction "OUT_P$2") (pintype "output"))
      (node (ref "CMP71") (pin "PORT1") (pinfunction "PORT1_PORT1") (pintype "input"))
    )
    (net (code "60") (name "BUS_R2_LEFT_SHIFTED") (class "Default")
      (node (ref "CMP16") (pin "P$2") (pinfunction "OUT_P$2") (pintype "output"))
      (node (ref "CMP70") (pin "PORT2") (pinfunction "PORT2_PORT2") (pintype "input"))
    )
    (net (code "61") (name "BUS_RA") (class "Default")
      (node (ref "CMP3") (pin "SRC") (pinfunction "SRC_SRC") (pintype "input"))
      (node (ref "CMP30") (pin "OUTB") (pinfunction "B_OUTB") (pintype "output"))
    )
    (net (code "62") (name "BUS_RA_A") (class "Default")
      (node (ref "CMP30") (pin "OUT_A") (pinfunction "A_OUT_A") (pintype "output"))
      (node (ref "CMP9") (pin "PORT0") (pinfunction "PORT0_PORT0") (pintype "input"))
    )
    (net (code "63") (name "BUS_RA_B") (class "Default")
      (node (ref "CMP3") (pin "1") (pinfunction "1_1") (pintype "output"))
      (node (ref "CMP7") (pin "INPUT") (pinfunction "INPUT_INPUT") (pintype "input"))
    )
    (net (code "64") (name "BUS_RA_C") (class "Default")
      (node (ref "CMP3") (pin "2") (pinfunction "2_2") (pintype "output"))
      (node (ref "CMP8") (pin "LSRC") (pinfunction "SRC_LSRC") (pintype "input"))
    )
    (net (code "65") (name "BUS_RA_D") (class "Default")
      (node (ref "CMP15") (pin "RSRC") (pinfunction "SRC_RSRC") (pintype "input"))
      (node (ref "CMP3") (pin "3") (pinfunction "3_3") (pintype "output"))
    )
    (net (code "66") (name "BUS_RA_FLAGS") (class "Default")
      (node (ref "CMP19") (pin "INPUT") (pinfunction "OUT_INPUT") (pintype "output"))
    )
    (net (code "67") (name "BUS_RB") (class "Default")
      (node (ref "CMP10") (pin "PORT2") (pinfunction "PORT2_PORT2") (pintype "input"))
      (node (ref "CMP5") (pin "P$2") (pinfunction "OUT_P$2") (pintype "output"))
    )
    (net (code "68") (name "BUS_RI") (class "Default")
      (node (ref "CMP6") (pin "P$2") (pinfunction "OUT_P$2") (pintype "output"))
      (node (ref "CMP70") (pin "PORT3") (pinfunction "PORT3_PORT3") (pintype "input"))
    )
    (net (code "69") (name "BUS_SHIFT_R3") (class "Default")
      (node (ref "CMP4") (pin "P$2") (pinfunction "OUT_P$2") (pintype "output"))
      (node (ref "CMP9") (pin "PORT1") (pinfunction "PORT1_PORT1") (pintype "input"))
    )
    (net (code "70") (name "BUS_SQRT_MASK") (class "Default")
      (node (ref "CMP12") (pin "P$2") (pinfunction "OUT_P$2") (pintype "output"))
      (node (ref "CMP70") (pin "PORT0") (pinfunction "PORT0_PORT0") (pintype "input"))
    )
    (net (code "71") (name "DO_SUBTRACT") (class "Default")
      (node (ref "CMP2") (pin "P$1") (pinfunction "OUT_0_P$1") (pintype "output"))
      (node (ref "CMP31") (pin "INV_B") (pinfunction "INV_B_INV_B") (pintype "input"))
      (node (ref "CMP32") (pin "INV_B") (pinfunction "INV_B_INV_B") (pintype "input"))
      (node (ref "CMP45") (pin "P$2") (pinfunction "A2_P$2") (pintype "input"))
    )
    (net (code "72") (name "D_MSB") (class "Default")
      (node (ref "CMP35") (pin "MS_BIT") (pinfunction "MS_BIT_MS_BIT") (pintype "output"))
      (node (ref "CMP39") (pin "A4") (pinfunction "IN_A4") (pintype "input"))
      (node (ref "CMP48") (pin "P$4") (pinfunction "B0_P$4") (pintype "input"))
      (node (ref "CMP49") (pin "P$5") (pinfunction "B1_P$5") (pintype "input"))
    )
    (net (code "73") (name "D_MSB_N") (class "Default")
      (node (ref "CMP39") (pin "N4") (pinfunction "N_N4") (pintype "output"))
      (node (ref "CMP48") (pin "P$3") (pinfunction "A2_P$3") (pintype "input"))
      (node (ref "CMP49") (pin "P$1") (pinfunction "A0_P$1") (pintype "input"))
    )
    (net (code "74") (name "H_4") (class "Default")
      (node (ref "CMP2") (pin "P$3") (pinfunction "OUT_2_P$3") (pintype "output"))
      (node (ref "CMP39") (pin "A1") (pinfunction "IN_A1") (pintype "input"))
    )
    (net (code "75") (name "INPUT_CARRY_BIT") (class "Default")
      (node (ref "CMP2") (pin "P$2") (pinfunction "OUT_1_P$2") (pintype "output"))
      (node (ref "CMP31") (pin "C_IN") (pinfunction "C_IN_C_IN") (pintype "input"))
    )
    (net (code "76") (name "INVER_BIT") (class "Default")
      (node (ref "CMP10") (pin "PORT1") (pinfunction "PORT1_PORT1") (pintype "input"))
      (node (ref "CMP14") (pin "INPUT") (pinfunction "OUT_INPUT") (pintype "output"))
    )
    (net (code "77") (name "IS_SHIFTING_LEFT") (class "Default")
      (node (ref "CMP2") (pin "P$13") (pinfunction "OUT_12_P$13") (pintype "output"))
      (node (ref "CMP60") (pin "EN0") (pinfunction "EN0_EN0") (pintype "input"))
    )
    (net (code "78") (name "IS_SHIFTING_RIGHT") (class "Default")
      (node (ref "CMP2") (pin "P$12") (pinfunction "OUT_11_P$12") (pintype "output"))
      (node (ref "CMP60") (pin "EN1") (pinfunction "EN1_EN1") (pintype "input"))
    )
    (net (code "79") (name "K_0") (class "Default")
      (node (ref "CMP1") (pin "P$14") (pinfunction "OUT_13_P$14") (pintype "output"))
      (node (ref "CMP93") (pin "P$1") (pinfunction "IN_0_P$1") (pintype "input"))
    )
    (net (code "80") (name "K_1") (class "Default")
      (node (ref "CMP1") (pin "P$13") (pinfunction "OUT_12_P$13") (pintype "output"))
      (node (ref "CMP93") (pin "P$2") (pinfunction "IN_1_P$2") (pintype "input"))
    )
    (net (code "81") (name "K_N") (class "Default")
      (node (ref "CMP1") (pin "P$12") (pinfunction "OUT_11_P$12") (pintype "output"))
      (node (ref "CMP93") (pin "P$10") (pinfunction "IN_9_P$10") (pintype "input"))
      (node (ref "CMP93") (pin "P$11") (pinfunction "IN_10_P$11") (pintype "input"))
      (node (ref "CMP93") (pin "P$12") (pinfunction "IN_11_P$12") (pintype "input"))
      (node (ref "CMP93") (pin "P$13") (pinfunction "IN_12_P$13") (pintype "input"))
      (node (ref "CMP93") (pin "P$14") (pinfunction "IN_13_P$14") (pintype "input"))
      (node (ref "CMP93") (pin "P$15") (pinfunction "IN_14_P$15") (pintype "input"))
      (node (ref "CMP93") (pin "P$16") (pinfunction "IN_15_P$16") (pintype "input"))
      (node (ref "CMP93") (pin "P$3") (pinfunction "IN_2_P$3") (pintype "input"))
      (node (ref "CMP93") (pin "P$4") (pinfunction "IN_3_P$4") (pintype "input"))
      (node (ref "CMP93") (pin "P$5") (pinfunction "IN_4_P$5") (pintype "input"))
      (node (ref "CMP93") (pin "P$6") (pinfunction "IN_5_P$6") (pintype "input"))
      (node (ref "CMP93") (pin "P$7") (pinfunction "IN_6_P$7") (pintype "input"))
      (node (ref "CMP93") (pin "P$8") (pinfunction "IN_7_P$8") (pintype "input"))
      (node (ref "CMP93") (pin "P$9") (pinfunction "IN_8_P$9") (pintype "input"))
    )
    (net (code "82") (name "LEFT_SHIFTER") (class "Default")
      (node (ref "CMP60") (pin "PORT0") (pinfunction "PORT0_PORT0") (pintype "input"))
      (node (ref "CMP8") (pin "RSRC") (pinfunction "OUT_RSRC") (pintype "output"))
    )
    (net (code "83") (name "LEFT_SHIFT_INPUT") (class "Default")
      (node (ref "CMP2") (pin "P$14") (pinfunction "OUT_13_P$14") (pintype "output"))
      (node (ref "CMP8") (pin "SHIFT_IN") (pinfunction "LSB_IN_SHIFT_IN") (pintype "input"))
    )
    (net (code "84") (name "LOGIC_OUT") (class "Default")
      (node (ref "CMP60") (pin "PORT3") (pinfunction "PORT3_PORT3") (pintype "input"))
      (node (ref "U$1") (pin "SRC") (pinfunction "WORD_SRC") (pintype "output"))
    )
    (net (code "85") (name "LOGIC_R_LSB") (class "Default")
      (node (ref "CMP47") (pin "R") (pinfunction "R_R") (pintype "output"))
      (node (ref "U$1") (pin "LSB_1") (pinfunction "LSB_1_LSB_1") (pintype "input"))
    )
    (net (code "86") (name "LOGIC_R_MSB") (class "Default")
      (node (ref "CMP46") (pin "R") (pinfunction "R_R") (pintype "output"))
      (node (ref "U$1") (pin "MSB_1") (pinfunction "MSB_1_MSB_1") (pintype "input"))
    )
    (net (code "87") (name "MASK_0") (class "Default")
      (node (ref "CMP11") (pin "P0") (pinfunction "P0_P0") (pintype "output"))
      (node (ref "CMP13") (pin "P$1") (pinfunction "IN_0_P$1") (pintype "input"))
      (node (ref "CMP54") (pin "P$2") (pinfunction "A1_P$2") (pintype "input"))
    )
    (net (code "88") (name "MASK_1") (class "Default")
      (node (ref "CMP11") (pin "P1") (pinfunction "P1_P1") (pintype "output"))
      (node (ref "CMP13") (pin "P$2") (pinfunction "IN_1_P$2") (pintype "input"))
      (node (ref "CMP54") (pin "P$4") (pinfunction "B1_P$4") (pintype "input"))
    )
    (net (code "89") (name "MASK_2") (class "Default")
      (node (ref "CMP11") (pin "P2") (pinfunction "P2_P2") (pintype "output"))
      (node (ref "CMP13") (pin "P$3") (pinfunction "IN_2_P$3") (pintype "input"))
      (node (ref "CMP54") (pin "P$6") (pinfunction "C1_P$6") (pintype "input"))
    )
    (net (code "90") (name "MASK_3") (class "Default")
      (node (ref "CMP11") (pin "P3") (pinfunction "P3_P3") (pintype "output"))
      (node (ref "CMP13") (pin "P$4") (pinfunction "IN_3_P$4") (pintype "input"))
      (node (ref "CMP54") (pin "P$8") (pinfunction "D1_P$8") (pintype "input"))
    )
    (net (code "91") (name "MASK_4") (class "Default")
      (node (ref "CMP11") (pin "P4") (pinfunction "P4_P4") (pintype "output"))
      (node (ref "CMP13") (pin "P$5") (pinfunction "IN_4_P$5") (pintype "input"))
      (node (ref "CMP54") (pin "P$10") (pinfunction "E2_P$10") (pintype "input"))
    )
    (net (code "92") (name "MASK_5") (class "Default")
      (node (ref "CMP11") (pin "P5") (pinfunction "P5_P5") (pintype "output"))
      (node (ref "CMP13") (pin "P$6") (pinfunction "IN_5_P$6") (pintype "input"))
      (node (ref "CMP54") (pin "P$12") (pinfunction "F2_P$12") (pintype "input"))
    )
    (net (code "93") (name "MASK_6") (class "Default")
      (node (ref "CMP11") (pin "P6") (pinfunction "P6_P6") (pintype "output"))
      (node (ref "CMP13") (pin "P$7") (pinfunction "IN_6_P$7") (pintype "input"))
      (node (ref "CMP54") (pin "P$14") (pinfunction "G2_P$14") (pintype "input"))
    )
    (net (code "94") (name "MASK_7") (class "Default")
      (node (ref "CMP11") (pin "P7") (pinfunction "P7_P7") (pintype "output"))
      (node (ref "CMP13") (pin "P$8") (pinfunction "IN_7_P$8") (pintype "input"))
      (node (ref "CMP54") (pin "P$16") (pinfunction "H2_P$16") (pintype "input"))
    )
    (net (code "95") (name "MASK_8") (class "Default")
      (node (ref "CMP11") (pin "P8") (pinfunction "P8_P8") (pintype "output"))
      (node (ref "CMP13") (pin "P$9") (pinfunction "IN_8_P$9") (pintype "input"))
      (node (ref "CMP53") (pin "P$2") (pinfunction "A1_P$2") (pintype "input"))
    )
    (net (code "96") (name "MASK_9") (class "Default")
      (node (ref "CMP11") (pin "P9") (pinfunction "P9_P9") (pintype "output"))
      (node (ref "CMP13") (pin "P$10") (pinfunction "IN_9_P$10") (pintype "input"))
      (node (ref "CMP53") (pin "P$4") (pinfunction "B1_P$4") (pintype "input"))
    )
    (net (code "97") (name "MASK_10") (class "Default")
      (node (ref "CMP11") (pin "P10") (pinfunction "P10_P10") (pintype "output"))
      (node (ref "CMP13") (pin "P$11") (pinfunction "IN_10_P$11") (pintype "input"))
      (node (ref "CMP53") (pin "P$6") (pinfunction "C1_P$6") (pintype "input"))
    )
    (net (code "98") (name "MASK_11") (class "Default")
      (node (ref "CMP11") (pin "P11") (pinfunction "P11_P11") (pintype "output"))
      (node (ref "CMP13") (pin "P$12") (pinfunction "IN_11_P$12") (pintype "input"))
      (node (ref "CMP53") (pin "P$8") (pinfunction "D1_P$8") (pintype "input"))
    )
    (net (code "99") (name "MASK_12") (class "Default")
      (node (ref "CMP11") (pin "P12") (pinfunction "P12_P12") (pintype "output"))
      (node (ref "CMP13") (pin "P$13") (pinfunction "IN_12_P$13") (pintype "input"))
      (node (ref "CMP53") (pin "P$10") (pinfunction "E2_P$10") (pintype "input"))
    )
    (net (code "100") (name "MASK_13") (class "Default")
      (node (ref "CMP11") (pin "P13") (pinfunction "P13_P13") (pintype "output"))
      (node (ref "CMP13") (pin "P$14") (pinfunction "IN_13_P$14") (pintype "input"))
      (node (ref "CMP53") (pin "P$12") (pinfunction "F2_P$12") (pintype "input"))
    )
    (net (code "101") (name "MASK_14") (class "Default")
      (node (ref "CMP11") (pin "P14") (pinfunction "P14_P14") (pintype "output"))
      (node (ref "CMP13") (pin "P$15") (pinfunction "IN_14_P$15") (pintype "input"))
      (node (ref "CMP53") (pin "P$14") (pinfunction "G2_P$14") (pintype "input"))
    )
    (net (code "102") (name "MASK_15") (class "Default")
      (node (ref "CMP11") (pin "P15") (pinfunction "P15_P15") (pintype "output"))
      (node (ref "CMP13") (pin "P$16") (pinfunction "IN_15_P$16") (pintype "input"))
      (node (ref "CMP53") (pin "P$16") (pinfunction "H2_P$16") (pintype "input"))
    )
    (net (code "103") (name "Net-(CMP9-PadEN2)") (class "Default")
      (node (ref "CMP9") (pin "EN2") (pinfunction "EN2_EN2") (pintype "input"))
      (node (ref "CMP9") (pin "EN3") (pinfunction "EN3_EN3") (pintype "input"))
    )
    (net (code "104") (name "Net-(CMP14-IN_0)") (class "Default")
      (node (ref "CMP11") (pin "N0") (pinfunction "N0_N0") (pintype "output"))
      (node (ref "CMP14") (pin "P$1") (pinfunction "IN_0_P$1") (pintype "input"))
    )
    (net (code "105") (name "Net-(CMP14-IN_1)") (class "Default")
      (node (ref "CMP11") (pin "N1") (pinfunction "N1_N1") (pintype "output"))
      (node (ref "CMP14") (pin "P$2") (pinfunction "IN_1_P$2") (pintype "input"))
    )
    (net (code "106") (name "Net-(CMP14-IN_2)") (class "Default")
      (node (ref "CMP11") (pin "N2") (pinfunction "N2_N2") (pintype "output"))
      (node (ref "CMP14") (pin "P$3") (pinfunction "IN_2_P$3") (pintype "input"))
    )
    (net (code "107") (name "Net-(CMP14-IN_3)") (class "Default")
      (node (ref "CMP11") (pin "N3") (pinfunction "N3_N3") (pintype "output"))
      (node (ref "CMP14") (pin "P$4") (pinfunction "IN_3_P$4") (pintype "input"))
    )
    (net (code "108") (name "Net-(CMP14-IN_4)") (class "Default")
      (node (ref "CMP11") (pin "N4") (pinfunction "N4_N4") (pintype "output"))
      (node (ref "CMP14") (pin "P$5") (pinfunction "IN_4_P$5") (pintype "input"))
    )
    (net (code "109") (name "Net-(CMP14-IN_5)") (class "Default")
      (node (ref "CMP11") (pin "N5") (pinfunction "N5_N5") (pintype "output"))
      (node (ref "CMP14") (pin "P$6") (pinfunction "IN_5_P$6") (pintype "input"))
    )
    (net (code "110") (name "Net-(CMP14-IN_6)") (class "Default")
      (node (ref "CMP11") (pin "N6") (pinfunction "N6_N6") (pintype "output"))
      (node (ref "CMP14") (pin "P$7") (pinfunction "IN_6_P$7") (pintype "input"))
    )
    (net (code "111") (name "Net-(CMP14-IN_7)") (class "Default")
      (node (ref "CMP11") (pin "N7") (pinfunction "N7_N7") (pintype "output"))
      (node (ref "CMP14") (pin "P$8") (pinfunction "IN_7_P$8") (pintype "input"))
    )
    (net (code "112") (name "Net-(CMP14-IN_8)") (class "Default")
      (node (ref "CMP11") (pin "N8") (pinfunction "N8_N8") (pintype "output"))
      (node (ref "CMP14") (pin "P$9") (pinfunction "IN_8_P$9") (pintype "input"))
    )
    (net (code "113") (name "Net-(CMP14-IN_9)") (class "Default")
      (node (ref "CMP11") (pin "N9") (pinfunction "N9_N9") (pintype "output"))
      (node (ref "CMP14") (pin "P$10") (pinfunction "IN_9_P$10") (pintype "input"))
    )
    (net (code "114") (name "Net-(CMP14-IN_10)") (class "Default")
      (node (ref "CMP11") (pin "N10") (pinfunction "N10_N10") (pintype "output"))
      (node (ref "CMP14") (pin "P$11") (pinfunction "IN_10_P$11") (pintype "input"))
    )
    (net (code "115") (name "Net-(CMP14-IN_11)") (class "Default")
      (node (ref "CMP11") (pin "N11") (pinfunction "N11_N11") (pintype "output"))
      (node (ref "CMP14") (pin "P$12") (pinfunction "IN_11_P$12") (pintype "input"))
    )
    (net (code "116") (name "Net-(CMP14-IN_12)") (class "Default")
      (node (ref "CMP11") (pin "N12") (pinfunction "N12_N12") (pintype "output"))
      (node (ref "CMP14") (pin "P$13") (pinfunction "IN_12_P$13") (pintype "input"))
    )
    (net (code "117") (name "Net-(CMP14-IN_13)") (class "Default")
      (node (ref "CMP11") (pin "N13") (pinfunction "N13_N13") (pintype "output"))
      (node (ref "CMP14") (pin "P$14") (pinfunction "IN_13_P$14") (pintype "input"))
    )
    (net (code "118") (name "Net-(CMP14-IN_14)") (class "Default")
      (node (ref "CMP11") (pin "N14") (pinfunction "N14_N14") (pintype "output"))
      (node (ref "CMP14") (pin "P$15") (pinfunction "IN_14_P$15") (pintype "input"))
    )
    (net (code "119") (name "Net-(CMP14-IN_15)") (class "Default")
      (node (ref "CMP11") (pin "N15") (pinfunction "N15_N15") (pintype "output"))
      (node (ref "CMP14") (pin "P$16") (pinfunction "IN_15_P$16") (pintype "input"))
    )
    (net (code "120") (name "Net-(CMP19-IN_10)") (class "Default")
      (node (ref "CMP19") (pin "P$10") (pinfunction "IN_9_P$10") (pintype "input"))
      (node (ref "CMP19") (pin "P$11") (pinfunction "IN_10_P$11") (pintype "input"))
      (node (ref "CMP19") (pin "P$12") (pinfunction "IN_11_P$12") (pintype "input"))
      (node (ref "CMP19") (pin "P$13") (pinfunction "IN_12_P$13") (pintype "input"))
      (node (ref "CMP19") (pin "P$14") (pinfunction "IN_13_P$14") (pintype "input"))
      (node (ref "CMP19") (pin "P$15") (pinfunction "IN_14_P$15") (pintype "input"))
      (node (ref "CMP19") (pin "P$16") (pinfunction "IN_15_P$16") (pintype "input"))
      (node (ref "CMP19") (pin "P$4") (pinfunction "IN_3_P$4") (pintype "input"))
      (node (ref "CMP19") (pin "P$5") (pinfunction "IN_4_P$5") (pintype "input"))
      (node (ref "CMP19") (pin "P$6") (pinfunction "IN_5_P$6") (pintype "input"))
      (node (ref "CMP19") (pin "P$7") (pinfunction "IN_6_P$7") (pintype "input"))
      (node (ref "CMP19") (pin "P$8") (pinfunction "IN_7_P$8") (pintype "input"))
      (node (ref "CMP19") (pin "P$9") (pinfunction "IN_8_P$9") (pintype "input"))
    )
    (net (code "121") (name "Net-(CMP25-IN_0)") (class "Default")
      (node (ref "CMP25") (pin "P$1") (pinfunction "IN_0_P$1") (pintype "input"))
      (node (ref "CMP25") (pin "P$10") (pinfunction "IN_9_P$10") (pintype "input"))
      (node (ref "CMP25") (pin "P$11") (pinfunction "IN_10_P$11") (pintype "input"))
      (node (ref "CMP25") (pin "P$12") (pinfunction "IN_11_P$12") (pintype "input"))
      (node (ref "CMP25") (pin "P$13") (pinfunction "IN_12_P$13") (pintype "input"))
      (node (ref "CMP25") (pin "P$14") (pinfunction "IN_13_P$14") (pintype "input"))
      (node (ref "CMP25") (pin "P$15") (pinfunction "IN_14_P$15") (pintype "input"))
      (node (ref "CMP25") (pin "P$16") (pinfunction "IN_15_P$16") (pintype "input"))
      (node (ref "CMP25") (pin "P$2") (pinfunction "IN_1_P$2") (pintype "input"))
      (node (ref "CMP25") (pin "P$3") (pinfunction "IN_2_P$3") (pintype "input"))
      (node (ref "CMP25") (pin "P$4") (pinfunction "IN_3_P$4") (pintype "input"))
      (node (ref "CMP25") (pin "P$5") (pinfunction "IN_4_P$5") (pintype "input"))
      (node (ref "CMP25") (pin "P$6") (pinfunction "IN_5_P$6") (pintype "input"))
      (node (ref "CMP25") (pin "P$7") (pinfunction "IN_6_P$7") (pintype "input"))
      (node (ref "CMP25") (pin "P$8") (pinfunction "IN_7_P$8") (pintype "input"))
      (node (ref "CMP25") (pin "P$9") (pinfunction "IN_8_P$9") (pintype "input"))
    )
    (net (code "122") (name "Net-(CMP28-IN_0)") (class "Default")
      (node (ref "CMP28") (pin "P$1") (pinfunction "IN_0_P$1") (pintype "input"))
      (node (ref "CMP28") (pin "P$10") (pinfunction "IN_9_P$10") (pintype "input"))
      (node (ref "CMP28") (pin "P$11") (pinfunction "IN_10_P$11") (pintype "input"))
      (node (ref "CMP28") (pin "P$12") (pinfunction "IN_11_P$12") (pintype "input"))
      (node (ref "CMP28") (pin "P$13") (pinfunction "IN_12_P$13") (pintype "input"))
      (node (ref "CMP28") (pin "P$14") (pinfunction "IN_13_P$14") (pintype "input"))
      (node (ref "CMP28") (pin "P$15") (pinfunction "IN_14_P$15") (pintype "input"))
      (node (ref "CMP28") (pin "P$16") (pinfunction "IN_15_P$16") (pintype "input"))
      (node (ref "CMP28") (pin "P$2") (pinfunction "IN_1_P$2") (pintype "input"))
      (node (ref "CMP28") (pin "P$3") (pinfunction "IN_2_P$3") (pintype "input"))
      (node (ref "CMP28") (pin "P$4") (pinfunction "IN_3_P$4") (pintype "input"))
      (node (ref "CMP28") (pin "P$5") (pinfunction "IN_4_P$5") (pintype "input"))
      (node (ref "CMP28") (pin "P$6") (pinfunction "IN_5_P$6") (pintype "input"))
      (node (ref "CMP28") (pin "P$7") (pinfunction "IN_6_P$7") (pintype "input"))
      (node (ref "CMP28") (pin "P$8") (pinfunction "IN_7_P$8") (pintype "input"))
      (node (ref "CMP28") (pin "P$9") (pinfunction "IN_8_P$9") (pintype "input"))
    )
    (net (code "123") (name "Net-(CMP33-IN)") (class "Default")
      (node (ref "CMP31") (pin "DISP") (pinfunction "DISP_DISP") (pintype "output"))
      (node (ref "CMP33") (pin "P$1") (pinfunction "IN_P$1") (pintype "input"))
    )
    (net (code "124") (name "Net-(CMP34-IN)") (class "Default")
      (node (ref "CMP32") (pin "DISP") (pinfunction "DISP_DISP") (pintype "output"))
      (node (ref "CMP34") (pin "P$1") (pinfunction "IN_P$1") (pintype "input"))
    )
    (net (code "125") (name "Net-(CMP41-IN)") (class "Default")
      (node (ref "CMP41") (pin "P$1") (pinfunction "IN_P$1") (pintype "input"))
      (node (ref "CMP47") (pin "DISP") (pinfunction "DISP_DISP") (pintype "output"))
    )
    (net (code "126") (name "Net-(CMP42-IN)") (class "Default")
      (node (ref "CMP42") (pin "P$1") (pinfunction "IN_P$1") (pintype "input"))
      (node (ref "CMP46") (pin "DISP") (pinfunction "DISP_DISP") (pintype "output"))
    )
    (net (code "127") (name "Net-(CMP51-IN_10)") (class "Default")
      (node (ref "CMP51") (pin "P$10") (pinfunction "IN_9_P$10") (pintype "input"))
      (node (ref "CMP51") (pin "P$11") (pinfunction "IN_10_P$11") (pintype "input"))
      (node (ref "CMP51") (pin "P$12") (pinfunction "IN_11_P$12") (pintype "input"))
      (node (ref "CMP51") (pin "P$13") (pinfunction "IN_12_P$13") (pintype "input"))
      (node (ref "CMP51") (pin "P$14") (pinfunction "IN_13_P$14") (pintype "input"))
      (node (ref "CMP51") (pin "P$15") (pinfunction "IN_14_P$15") (pintype "input"))
      (node (ref "CMP51") (pin "P$16") (pinfunction "IN_15_P$16") (pintype "input"))
    )
    (net (code "128") (name "Net-(CMP52-A0)") (class "Default")
      (node (ref "CMP52") (pin "P$1") (pinfunction "A0_P$1") (pintype "input"))
      (node (ref "CMP52") (pin "P$2") (pinfunction "A1_P$2") (pintype "input"))
    )
    (net (code "129") (name "Net-(CMP53-P)") (class "Default")
      (node (ref "CMP53") (pin "OUT_P") (pinfunction "P_OUT_P") (pintype "output"))
      (node (ref "CMP55") (pin "P$2") (pinfunction "A1_P$2") (pintype "input"))
    )
    (net (code "130") (name "Net-(CMP54-P)") (class "Default")
      (node (ref "CMP54") (pin "OUT_P") (pinfunction "P_OUT_P") (pintype "output"))
      (node (ref "CMP55") (pin "P$1") (pinfunction "A2_P$1") (pintype "input"))
    )
    (net (code "131") (name "Net-(CMP72-IN_1)") (class "Default")
      (node (ref "CMP72") (pin "P$10") (pinfunction "IN_9_P$10") (pintype "input"))
      (node (ref "CMP72") (pin "P$11") (pinfunction "IN_10_P$11") (pintype "input"))
      (node (ref "CMP72") (pin "P$12") (pinfunction "IN_11_P$12") (pintype "input"))
      (node (ref "CMP72") (pin "P$13") (pinfunction "IN_12_P$13") (pintype "input"))
      (node (ref "CMP72") (pin "P$14") (pinfunction "IN_13_P$14") (pintype "input"))
      (node (ref "CMP72") (pin "P$15") (pinfunction "IN_14_P$15") (pintype "input"))
      (node (ref "CMP72") (pin "P$16") (pinfunction "IN_15_P$16") (pintype "input"))
      (node (ref "CMP72") (pin "P$2") (pinfunction "IN_1_P$2") (pintype "input"))
      (node (ref "CMP72") (pin "P$3") (pinfunction "IN_2_P$3") (pintype "input"))
      (node (ref "CMP72") (pin "P$4") (pinfunction "IN_3_P$4") (pintype "input"))
      (node (ref "CMP72") (pin "P$5") (pinfunction "IN_4_P$5") (pintype "input"))
      (node (ref "CMP72") (pin "P$6") (pinfunction "IN_5_P$6") (pintype "input"))
      (node (ref "CMP72") (pin "P$7") (pinfunction "IN_6_P$7") (pintype "input"))
      (node (ref "CMP72") (pin "P$8") (pinfunction "IN_7_P$8") (pintype "input"))
      (node (ref "CMP72") (pin "P$9") (pinfunction "IN_8_P$9") (pintype "input"))
    )
    (net (code "132") (name "Net-(CMP84-IN)") (class "Default")
      (node (ref "CMP82") (pin "DISP") (pinfunction "DISP_DISP") (pintype "output"))
      (node (ref "CMP84") (pin "P$1") (pinfunction "IN_P$1") (pintype "input"))
    )
    (net (code "133") (name "Net-(CMP85-IN)") (class "Default")
      (node (ref "CMP83") (pin "DISP") (pinfunction "DISP_DISP") (pintype "output"))
      (node (ref "CMP85") (pin "P$1") (pinfunction "IN_P$1") (pintype "input"))
    )
    (net (code "134") (name "OR") (class "Default")
      (node (ref "CMP2") (pin "P$5") (pinfunction "OUT_4_P$5") (pintype "output"))
      (node (ref "CMP46") (pin "OR") (pinfunction "OR_OR") (pintype "input"))
      (node (ref "CMP47") (pin "OR") (pinfunction "OR_OR") (pintype "input"))
    )
    (net (code "135") (name "PLUS_1") (class "Default")
      (node (ref "CMP71") (pin "PORT0") (pinfunction "PORT0_PORT0") (pintype "input"))
      (node (ref "CMP72") (pin "INPUT") (pinfunction "OUT_INPUT") (pintype "output"))
    )
    (net (code "136") (name "RA_0") (class "Default")
      (node (ref "CMP54") (pin "P$1") (pinfunction "A0_P$1") (pintype "input"))
      (node (ref "CMP7") (pin "P$1") (pinfunction "OUT_0_P$1") (pintype "output"))
    )
    (net (code "137") (name "RA_1") (class "Default")
      (node (ref "CMP54") (pin "P$3") (pinfunction "B0_P$3") (pintype "input"))
      (node (ref "CMP7") (pin "P$2") (pinfunction "OUT_1_P$2") (pintype "output"))
    )
    (net (code "138") (name "RA_2") (class "Default")
      (node (ref "CMP54") (pin "P$5") (pinfunction "C0_P$5") (pintype "input"))
      (node (ref "CMP7") (pin "P$3") (pinfunction "OUT_2_P$3") (pintype "output"))
    )
    (net (code "139") (name "RA_3") (class "Default")
      (node (ref "CMP54") (pin "P$7") (pinfunction "D0_P$7") (pintype "input"))
      (node (ref "CMP7") (pin "P$4") (pinfunction "OUT_3_P$4") (pintype "output"))
    )
    (net (code "140") (name "RA_4") (class "Default")
      (node (ref "CMP54") (pin "P$9") (pinfunction "E1_P$9") (pintype "input"))
      (node (ref "CMP7") (pin "P$5") (pinfunction "OUT_4_P$5") (pintype "output"))
    )
    (net (code "141") (name "RA_5") (class "Default")
      (node (ref "CMP54") (pin "P$11") (pinfunction "F1_P$11") (pintype "input"))
      (node (ref "CMP7") (pin "P$6") (pinfunction "OUT_5_P$6") (pintype "output"))
    )
    (net (code "142") (name "RA_6") (class "Default")
      (node (ref "CMP54") (pin "P$13") (pinfunction "G1_P$13") (pintype "input"))
      (node (ref "CMP7") (pin "P$7") (pinfunction "OUT_6_P$7") (pintype "output"))
    )
    (net (code "143") (name "RA_7") (class "Default")
      (node (ref "CMP54") (pin "P$15") (pinfunction "H1_P$15") (pintype "input"))
      (node (ref "CMP7") (pin "P$8") (pinfunction "OUT_7_P$8") (pintype "output"))
    )
    (net (code "144") (name "RA_8") (class "Default")
      (node (ref "CMP53") (pin "P$1") (pinfunction "A0_P$1") (pintype "input"))
      (node (ref "CMP7") (pin "P$9") (pinfunction "OUT_8_P$9") (pintype "output"))
    )
    (net (code "145") (name "RA_9") (class "Default")
      (node (ref "CMP53") (pin "P$3") (pinfunction "B0_P$3") (pintype "input"))
      (node (ref "CMP7") (pin "P$10") (pinfunction "OUT_9_P$10") (pintype "output"))
    )
    (net (code "146") (name "RA_10") (class "Default")
      (node (ref "CMP53") (pin "P$5") (pinfunction "C0_P$5") (pintype "input"))
      (node (ref "CMP7") (pin "P$11") (pinfunction "OUT_10_P$11") (pintype "output"))
    )
    (net (code "147") (name "RA_11") (class "Default")
      (node (ref "CMP53") (pin "P$7") (pinfunction "D0_P$7") (pintype "input"))
      (node (ref "CMP7") (pin "P$12") (pinfunction "OUT_11_P$12") (pintype "output"))
    )
    (net (code "148") (name "RA_12") (class "Default")
      (node (ref "CMP53") (pin "P$9") (pinfunction "E1_P$9") (pintype "input"))
      (node (ref "CMP7") (pin "P$13") (pinfunction "OUT_12_P$13") (pintype "output"))
    )
    (net (code "149") (name "RA_13") (class "Default")
      (node (ref "CMP53") (pin "P$11") (pinfunction "F1_P$11") (pintype "input"))
      (node (ref "CMP7") (pin "P$14") (pinfunction "OUT_13_P$14") (pintype "output"))
    )
    (net (code "150") (name "RA_14") (class "Default")
      (node (ref "CMP38") (pin "P$2") (pinfunction "A2_P$2") (pintype "input"))
      (node (ref "CMP53") (pin "P$13") (pinfunction "G1_P$13") (pintype "input"))
      (node (ref "CMP7") (pin "P$15") (pinfunction "OUT_14_P$15") (pintype "output"))
    )
    (net (code "151") (name "RA_15") (class "Default")
      (node (ref "CMP53") (pin "P$15") (pinfunction "H1_P$15") (pintype "input"))
      (node (ref "CMP7") (pin "P$16") (pinfunction "OUT_15_P$16") (pintype "output"))
    )
    (net (code "152") (name "RA_IS_Z") (class "Default")
      (node (ref "CMP15") (pin "IS_ZERO") (pinfunction "IS_ZERO_IS_ZERO") (pintype "output"))
      (node (ref "CMP19") (pin "P$2") (pinfunction "IN_1_P$2") (pintype "input"))
      (node (ref "CMP51") (pin "P$7") (pinfunction "IN_6_P$7") (pintype "input"))
    )
    (net (code "153") (name "RA_LSB") (class "Default")
      (node (ref "CMP15") (pin "LSB") (pinfunction "LSB_LSB") (pintype "output"))
      (node (ref "CMP19") (pin "P$3") (pinfunction "IN_2_P$3") (pintype "input"))
      (node (ref "CMP56") (pin "P$1") (pinfunction "A0_P$1") (pintype "input"))
    )
    (net (code "154") (name "RA_MSB") (class "Default")
      (node (ref "CMP15") (pin "MSB") (pinfunction "MSB_MSB") (pintype "output"))
      (node (ref "CMP19") (pin "P$1") (pinfunction "IN_0_P$1") (pintype "input"))
      (node (ref "CMP38") (pin "P$1") (pinfunction "A1_P$1") (pintype "input"))
      (node (ref "CMP51") (pin "P$8") (pinfunction "IN_7_P$8") (pintype "input"))
      (node (ref "CMP56") (pin "P$3") (pinfunction "B0_P$3") (pintype "input"))
    )
    (net (code "155") (name "RIGHT_SHIFTER") (class "Default")
      (node (ref "CMP15") (pin "LSRC") (pinfunction "OUT_LSRC") (pintype "output"))
      (node (ref "CMP60") (pin "PORT1") (pinfunction "PORT1_PORT1") (pintype "input"))
    )
    (net (code "156") (name "RIGHT_SHIFT_INPUT") (class "Default")
      (node (ref "CMP15") (pin "SHIFT_IN") (pinfunction "LSB_IN_SHIFT_IN") (pintype "input"))
      (node (ref "CMP2") (pin "P$15") (pinfunction "OUT_14_P$15") (pintype "output"))
    )
    (net (code "157") (name "R_MSB") (class "Default")
      (node (ref "CMP39") (pin "A2") (pinfunction "IN_A2") (pintype "input"))
      (node (ref "CMP48") (pin "P$2") (pinfunction "A1_P$2") (pintype "input"))
      (node (ref "CMP49") (pin "P$3") (pinfunction "A2_P$3") (pintype "input"))
      (node (ref "CMP50") (pin "P$2") (pinfunction "2_P$2") (pintype "input"))
      (node (ref "CMP51") (pin "P$3") (pinfunction "IN_2_P$3") (pintype "input"))
      (node (ref "U$8") (pin "MS_BIT") (pinfunction "MS_BIT_MS_BIT") (pintype "output"))
    )
    (net (code "158") (name "R_MSB_N") (class "Default")
      (node (ref "CMP39") (pin "N2") (pinfunction "N_N2") (pintype "output"))
      (node (ref "CMP48") (pin "P$5") (pinfunction "B1_P$5") (pintype "input"))
      (node (ref "CMP49") (pin "P$4") (pinfunction "B0_P$4") (pintype "input"))
    )
    (net (code "159") (name "SHIFT_LEFT") (class "Default")
      (node (ref "CMP39") (pin "N1") (pinfunction "N_N1") (pintype "output"))
      (node (ref "CMP56") (pin "P$4") (pinfunction "B1_P$4") (pintype "input"))
    )
    (net (code "160") (name "SHIFT_RESULT_C_FLAG") (class "Default")
      (node (ref "CMP51") (pin "P$4") (pinfunction "IN_3_P$4") (pintype "input"))
      (node (ref "CMP56") (pin "OUT_P") (pinfunction "P_OUT_P") (pintype "output"))
    )
    (net (code "161") (name "SHIFT_RESULT_V_FLAG") (class "Default")
      (node (ref "CMP38") (pin "OUT_P") (pinfunction "P_OUT_P") (pintype "output"))
      (node (ref "CMP51") (pin "P$6") (pinfunction "IN_5_P$6") (pintype "input"))
    )
    (net (code "162") (name "SHIFT_RIGHT") (class "Default")
      (node (ref "CMP39") (pin "P1") (pinfunction "P_P1") (pintype "output"))
      (node (ref "CMP56") (pin "P$2") (pinfunction "A1_P$2") (pintype "input"))
    )
    (net (code "163") (name "S_MSB") (class "Default")
      (node (ref "CMP36") (pin "MS_BIT") (pinfunction "MS_BIT_MS_BIT") (pintype "output"))
      (node (ref "CMP39") (pin "A3") (pinfunction "IN_A3") (pintype "input"))
      (node (ref "CMP48") (pin "P$6") (pinfunction "B2_P$6") (pintype "input"))
      (node (ref "CMP49") (pin "P$2") (pinfunction "A1_P$2") (pintype "input"))
      (node (ref "CMP50") (pin "P$1") (pinfunction "1_P$1") (pintype "input"))
    )
    (net (code "164") (name "S_MSB_N") (class "Default")
      (node (ref "CMP39") (pin "N3") (pinfunction "N_N3") (pintype "output"))
      (node (ref "CMP48") (pin "P$1") (pinfunction "A0_P$1") (pintype "input"))
      (node (ref "CMP49") (pin "P$6") (pinfunction "B2_P$6") (pintype "input"))
    )
    (net (code "165") (name "USE_ADD_V") (class "Default")
      (node (ref "CMP2") (pin "P$7") (pinfunction "OUT_6_P$7") (pintype "output"))
      (node (ref "CMP52") (pin "P$7") (pinfunction "D0_P$7") (pintype "input"))
    )
    (net (code "166") (name "USE_NEG_V") (class "Default")
      (node (ref "CMP2") (pin "P$9") (pinfunction "OUT_8_P$9") (pintype "output"))
      (node (ref "CMP52") (pin "P$3") (pinfunction "B0_P$3") (pintype "input"))
    )
    (net (code "167") (name "USE_SUB_V") (class "Default")
      (node (ref "CMP2") (pin "P$8") (pinfunction "OUT_7_P$8") (pintype "output"))
      (node (ref "CMP52") (pin "P$5") (pinfunction "C0_P$5") (pintype "input"))
    )
    (net (code "168") (name "X") (class "Default")
      (node (ref "CMP35") (pin "SRC") (pinfunction "SRC_SRC") (pintype "input"))
      (node (ref "CMP9") (pin "PORTOUT") (pinfunction "OUTPUT_PORTOUT") (pintype "output"))
    )
    (net (code "169") (name "XOR") (class "Default")
      (node (ref "CMP2") (pin "P$4") (pinfunction "OUT_3_P$4") (pintype "output"))
      (node (ref "CMP46") (pin "XOR") (pinfunction "XOR_XOR") (pintype "input"))
      (node (ref "CMP47") (pin "XOR") (pinfunction "XOR_XOR") (pintype "input"))
    )
    (net (code "170") (name "X_LSB_A") (class "Default")
      (node (ref "CMP31") (pin "A") (pinfunction "A_A") (pintype "input"))
      (node (ref "CMP35") (pin "LSB_2") (pinfunction "LSB_2_LSB_2") (pintype "output"))
    )
    (net (code "171") (name "X_LSB_B") (class "Default")
      (node (ref "CMP35") (pin "LSB_1") (pinfunction "LSB_1_LSB_1") (pintype "output"))
      (node (ref "CMP47") (pin "A") (pinfunction "A_A") (pintype "input"))
    )
    (net (code "172") (name "X_MSB_A") (class "Default")
      (node (ref "CMP32") (pin "A") (pinfunction "A_A") (pintype "input"))
      (node (ref "CMP35") (pin "MSB_2") (pinfunction "MSB_2_MSB_2") (pintype "output"))
    )
    (net (code "173") (name "X_MSB_B") (class "Default")
      (node (ref "CMP35") (pin "MSB_1") (pinfunction "MSB_1_MSB_1") (pintype "output"))
      (node (ref "CMP46") (pin "A") (pinfunction "A_A") (pintype "input"))
    )
    (net (code "174") (name "Y") (class "Default")
      (node (ref "CMP10") (pin "PORTOUT") (pinfunction "OUTPUT_PORTOUT") (pintype "output"))
      (node (ref "CMP36") (pin "SRC") (pinfunction "SRC_SRC") (pintype "input"))
    )
    (net (code "175") (name "Y_LSB_A") (class "Default")
      (node (ref "CMP31") (pin "B") (pinfunction "B_B") (pintype "input"))
      (node (ref "CMP36") (pin "LSB_1") (pinfunction "LSB_1_LSB_1") (pintype "output"))
    )
    (net (code "176") (name "Y_LSB_B") (class "Default")
      (node (ref "CMP36") (pin "LSB_2") (pinfunction "LSB_2_LSB_2") (pintype "output"))
      (node (ref "CMP47") (pin "B") (pinfunction "B_B") (pintype "input"))
    )
    (net (code "177") (name "Y_MSB_A") (class "Default")
      (node (ref "CMP32") (pin "B") (pinfunction "B_B") (pintype "input"))
      (node (ref "CMP36") (pin "MSB_1") (pinfunction "MSB_1_MSB_1") (pintype "output"))
    )
    (net (code "178") (name "Y_MSB_B") (class "Default")
      (node (ref "CMP36") (pin "MSB_2") (pinfunction "MSB_2_MSB_2") (pintype "output"))
      (node (ref "CMP46") (pin "B") (pinfunction "B_B") (pintype "input"))
    )
    (net (code "179") (name "ZERO_A") (class "Default")
      (node (ref "CMP25") (pin "INPUT") (pinfunction "OUT_INPUT") (pintype "output"))
      (node (ref "CMP9") (pin "PORT3") (pinfunction "PORT3_PORT3") (pintype "input"))
    )
    (net (code "180") (name "ZERO_B") (class "Default")
      (node (ref "CMP28") (pin "INPUT") (pinfunction "OUT_INPUT") (pintype "output"))
      (node (ref "CMP9") (pin "PORT2") (pinfunction "PORT2_PORT2") (pintype "input"))
    )
    (net (code "181") (name "unconnected-(CMP1-OUT_14-PadP$15)") (class "Default")
      (node (ref "CMP1") (pin "P$15") (pinfunction "OUT_14_P$15") (pintype "output"))
    )
    (net (code "182") (name "unconnected-(CMP1-OUT_15-PadP$16)") (class "Default")
      (node (ref "CMP1") (pin "P$16") (pinfunction "OUT_15_P$16") (pintype "output"))
    )
    (net (code "183") (name "unconnected-(CMP2-OUT_15-PadP$16)") (class "Default")
      (node (ref "CMP2") (pin "P$16") (pinfunction "OUT_15_P$16") (pintype "output"))
    )
    (net (code "184") (name "unconnected-(CMP3-Pad4)") (class "Default")
      (node (ref "CMP3") (pin "4") (pinfunction "4_4") (pintype "output"))
    )
    (net (code "185") (name "unconnected-(CMP4-IN-PadP$1)") (class "Default")
      (node (ref "CMP4") (pin "P$1") (pinfunction "IN_P$1") (pintype "input"))
    )
    (net (code "186") (name "unconnected-(CMP5-IN-PadP$1)") (class "Default")
      (node (ref "CMP5") (pin "P$1") (pinfunction "IN_P$1") (pintype "input"))
    )
    (net (code "187") (name "unconnected-(CMP6-IN-PadP$1)") (class "Default")
      (node (ref "CMP6") (pin "P$1") (pinfunction "IN_P$1") (pintype "input"))
    )
    (net (code "188") (name "unconnected-(CMP8-SRC_LSB-PadLSB)") (class "Default")
      (node (ref "CMP8") (pin "LSB") (pinfunction "SRC_LSB_LSB") (pintype "output"))
    )
    (net (code "189") (name "unconnected-(CMP8-SRC_MSB-PadMSB)") (class "Default")
      (node (ref "CMP8") (pin "MSB") (pinfunction "SRC_MSB_MSB") (pintype "output"))
    )
    (net (code "190") (name "unconnected-(CMP8-SRC_ZERO-PadIS_ZERO)") (class "Default")
      (node (ref "CMP8") (pin "IS_ZERO") (pinfunction "SRC_ZERO_IS_ZERO") (pintype "output"))
    )
    (net (code "191") (name "unconnected-(CMP12-IN-PadP$1)") (class "Default")
      (node (ref "CMP12") (pin "P$1") (pinfunction "IN_P$1") (pintype "input"))
    )
    (net (code "192") (name "unconnected-(CMP16-IN-PadP$1)") (class "Default")
      (node (ref "CMP16") (pin "P$1") (pinfunction "IN_P$1") (pintype "input"))
    )
    (net (code "193") (name "unconnected-(CMP17-IN-PadP$1)") (class "Default")
      (node (ref "CMP17") (pin "P$1") (pinfunction "IN_P$1") (pintype "input"))
    )
    (net (code "194") (name "unconnected-(CMP18-N-PadOUT_N)") (class "Default")
      (node (ref "CMP18") (pin "OUT_N") (pinfunction "N_OUT_N") (pintype "output"))
    )
    (net (code "195") (name "unconnected-(CMP24-IN-PadP$1)") (class "Default")
      (node (ref "CMP24") (pin "P$1") (pinfunction "IN_P$1") (pintype "input"))
    )
    (net (code "196") (name "unconnected-(CMP26-PadLSB_2)") (class "Default")
      (node (ref "CMP26") (pin "LSB_2") (pinfunction "LSB_2_LSB_2") (pintype "output"))
    )
    (net (code "197") (name "unconnected-(CMP26-PadMSB_2)") (class "Default")
      (node (ref "CMP26") (pin "MSB_2") (pinfunction "MSB_2_MSB_2") (pintype "output"))
    )
    (net (code "198") (name "unconnected-(CMP27-PadLSB_2)") (class "Default")
      (node (ref "CMP27") (pin "LSB_2") (pinfunction "LSB_2_LSB_2") (pintype "output"))
    )
    (net (code "199") (name "unconnected-(CMP27-PadMSB_2)") (class "Default")
      (node (ref "CMP27") (pin "MSB_2") (pinfunction "MSB_2_MSB_2") (pintype "output"))
    )
    (net (code "200") (name "unconnected-(CMP30-IN-PadINPUT)") (class "Default")
      (node (ref "CMP30") (pin "INPUT") (pinfunction "IN_INPUT") (pintype "input"))
    )
    (net (code "201") (name "unconnected-(CMP38-N-PadOUT_N)") (class "Default")
      (node (ref "CMP38") (pin "OUT_N") (pinfunction "N_OUT_N") (pintype "output"))
    )
    (net (code "202") (name "unconnected-(CMP39B-P-PadP2)") (class "Default")
      (node (ref "CMP39") (pin "P2") (pinfunction "P_P2") (pintype "output"))
    )
    (net (code "203") (name "unconnected-(CMP39C-P-PadP3)") (class "Default")
      (node (ref "CMP39") (pin "P3") (pinfunction "P_P3") (pintype "output"))
    )
    (net (code "204") (name "unconnected-(CMP39D-P-PadP4)") (class "Default")
      (node (ref "CMP39") (pin "P4") (pinfunction "P_P4") (pintype "output"))
    )
    (net (code "205") (name "unconnected-(CMP45-N-PadOUT_N)") (class "Default")
      (node (ref "CMP45") (pin "OUT_N") (pinfunction "N_OUT_N") (pintype "output"))
    )
    (net (code "206") (name "unconnected-(CMP48-N-PadOUT_M)") (class "Default")
      (node (ref "CMP48") (pin "OUT_M") (pinfunction "N_OUT_M") (pintype "output"))
    )
    (net (code "207") (name "unconnected-(CMP49-N-PadOUT_M)") (class "Default")
      (node (ref "CMP49") (pin "OUT_M") (pinfunction "N_OUT_M") (pintype "output"))
    )
    (net (code "208") (name "unconnected-(CMP50-N-PadOUT_M)") (class "Default")
      (node (ref "CMP50") (pin "OUT_M") (pinfunction "N_OUT_M") (pintype "output"))
    )
    (net (code "209") (name "unconnected-(CMP52-N-PadOUT_M)") (class "Default")
      (node (ref "CMP52") (pin "OUT_M") (pinfunction "N_OUT_M") (pintype "output"))
    )
    (net (code "210") (name "unconnected-(CMP53-N-PadOUT_M)") (class "Default")
      (node (ref "CMP53") (pin "OUT_M") (pinfunction "N_OUT_M") (pintype "output"))
    )
    (net (code "211") (name "unconnected-(CMP54-N-PadOUT_M)") (class "Default")
      (node (ref "CMP54") (pin "OUT_M") (pinfunction "N_OUT_M") (pintype "output"))
    )
    (net (code "212") (name "unconnected-(CMP55-P-PadOUT_P)") (class "Default")
      (node (ref "CMP55") (pin "OUT_P") (pinfunction "P_OUT_P") (pintype "output"))
    )
    (net (code "213") (name "unconnected-(CMP56-N-PadOUT_M)") (class "Default")
      (node (ref "CMP56") (pin "OUT_M") (pinfunction "N_OUT_M") (pintype "output"))
    )
    (net (code "214") (name "unconnected-(CMP61-OUT-PadP$2)") (class "Default")
      (node (ref "CMP61") (pin "P$2") (pinfunction "OUT_P$2") (pintype "output"))
    )
    (net (code "215") (name "unconnected-(CMP66-IN-PadP$1)") (class "Default")
      (node (ref "CMP66") (pin "P$1") (pinfunction "IN_P$1") (pintype "input"))
    )
    (net (code "216") (name "unconnected-(CMP68-IN-PadP$1)") (class "Default")
      (node (ref "CMP68") (pin "P$1") (pinfunction "IN_P$1") (pintype "input"))
    )
    (net (code "217") (name "unconnected-(CMP69-OUT_10-PadP$11)") (class "Default")
      (node (ref "CMP69") (pin "P$11") (pinfunction "OUT_10_P$11") (pintype "output"))
    )
    (net (code "218") (name "unconnected-(CMP69-OUT_11-PadP$12)") (class "Default")
      (node (ref "CMP69") (pin "P$12") (pinfunction "OUT_11_P$12") (pintype "output"))
    )
    (net (code "219") (name "unconnected-(CMP69-OUT_12-PadP$13)") (class "Default")
      (node (ref "CMP69") (pin "P$13") (pinfunction "OUT_12_P$13") (pintype "output"))
    )
    (net (code "220") (name "unconnected-(CMP69-OUT_13-PadP$14)") (class "Default")
      (node (ref "CMP69") (pin "P$14") (pinfunction "OUT_13_P$14") (pintype "output"))
    )
    (net (code "221") (name "unconnected-(CMP69-OUT_14-PadP$15)") (class "Default")
      (node (ref "CMP69") (pin "P$15") (pinfunction "OUT_14_P$15") (pintype "output"))
    )
    (net (code "222") (name "unconnected-(CMP69-OUT_15-PadP$16)") (class "Default")
      (node (ref "CMP69") (pin "P$16") (pinfunction "OUT_15_P$16") (pintype "output"))
    )
    (net (code "223") (name "unconnected-(CMP72-IN_0-PadP$1)") (class "Default")
      (node (ref "CMP72") (pin "P$1") (pinfunction "IN_0_P$1") (pintype "input"))
    )
    (net (code "224") (name "unconnected-(U$1-PadLSB_2)") (class "Default")
      (node (ref "U$1") (pin "LSB_2") (pinfunction "LSB_2_LSB_2") (pintype "input"))
    )
    (net (code "225") (name "unconnected-(U$1-PadMSB_2)") (class "Default")
      (node (ref "U$1") (pin "MSB_2") (pinfunction "MSB_2_MSB_2") (pintype "input"))
    )
    (net (code "226") (name "unconnected-(U$1-PadMS_BIT)") (class "Default")
      (node (ref "U$1") (pin "MS_BIT") (pinfunction "MS_BIT_MS_BIT") (pintype "output"))
    )
    (net (code "227") (name "unconnected-(U$3-PadLSB_1)") (class "Default")
      (node (ref "U$3") (pin "LSB_1") (pinfunction "LSB_1_LSB_1") (pintype "input"))
    )
    (net (code "228") (name "unconnected-(U$3-PadMSB_1)") (class "Default")
      (node (ref "U$3") (pin "MSB_1") (pinfunction "MSB_1_MSB_1") (pintype "input"))
    )
    (net (code "229") (name "unconnected-(U$3-PadMS_BIT)") (class "Default")
      (node (ref "U$3") (pin "MS_BIT") (pinfunction "MS_BIT_MS_BIT") (pintype "output"))
    )
    (net (code "230") (name "unconnected-(U$3-WORD-PadSRC)") (class "Default")
      (node (ref "U$3") (pin "SRC") (pinfunction "WORD_SRC") (pintype "output"))
    )
    (net (code "231") (name "unconnected-(U$8-PadLSB_2)") (class "Default")
      (node (ref "U$8") (pin "LSB_2") (pinfunction "LSB_2_LSB_2") (pintype "input"))
    )
    (net (code "232") (name "unconnected-(U$8-PadMSB_1)") (class "Default")
      (node (ref "U$8") (pin "MSB_1") (pinfunction "MSB_1_MSB_1") (pintype "input"))
    )
  )
)
